# main.net
KiCad netlist of a schematic drawn in Altium Designer
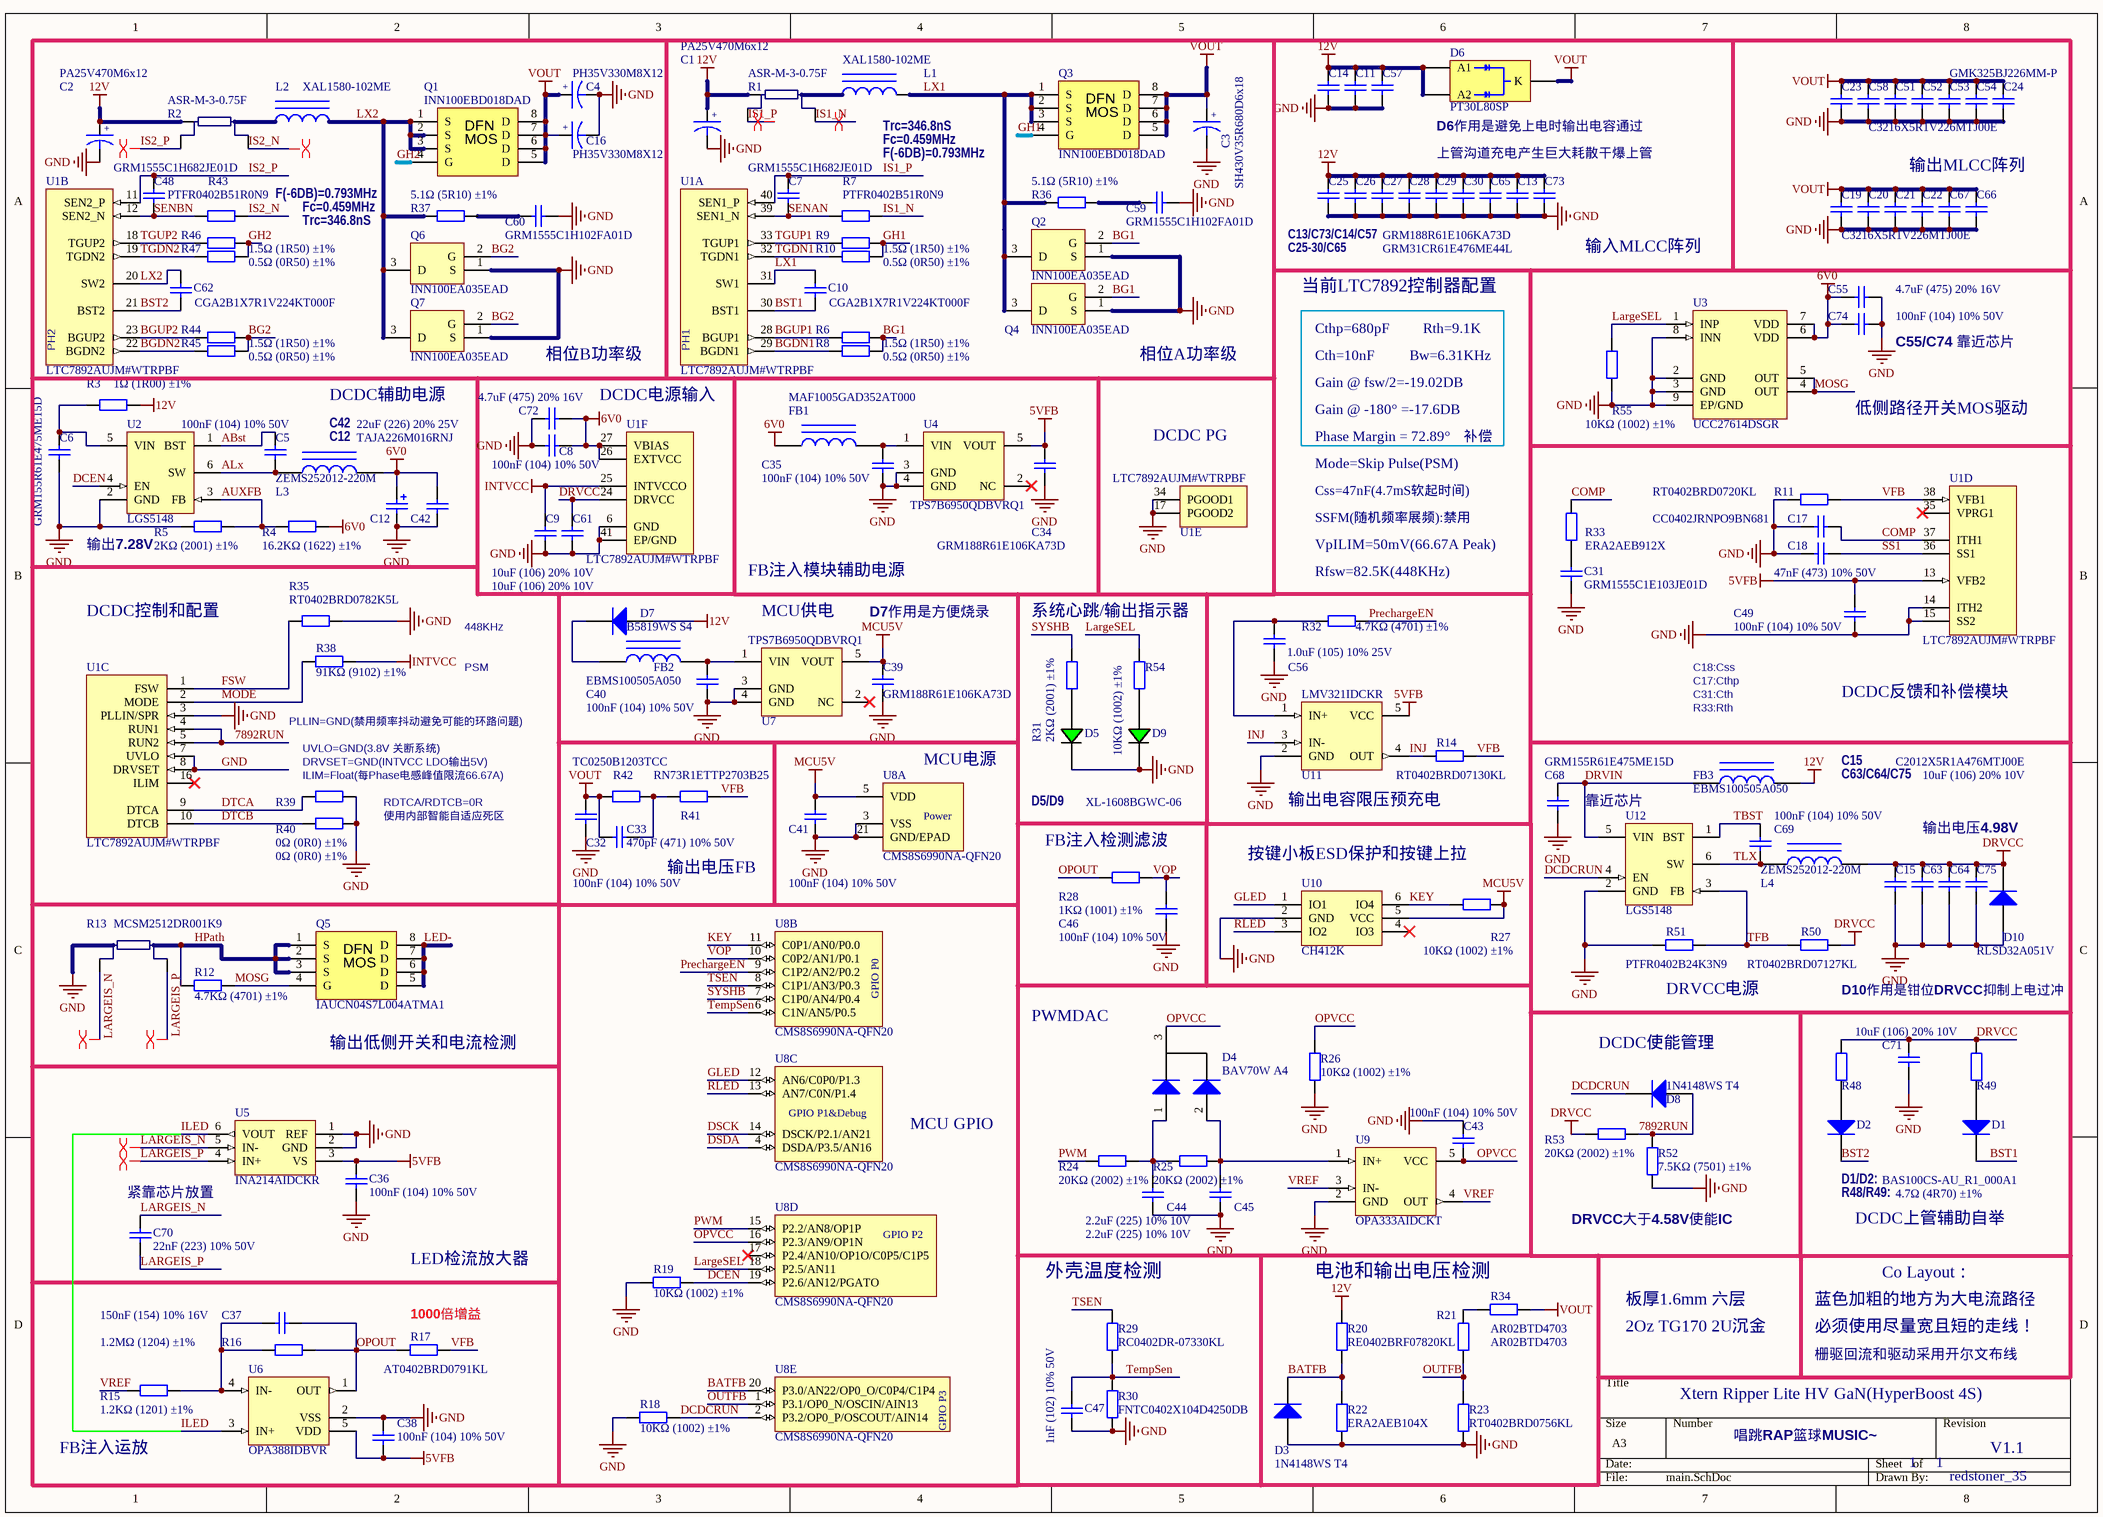
[diagram p0: main.SchDoc]

(export (version "E")
  (design (tool "Eeschema 10.0.6"))
  (components
    (comp (ref "C1")
      (value "PA25V470M6x12")
      (footprint "ElecCap_Hori")
      (description "直插固态电容，耐压25V容量470uF，尺寸D6.3x12")
      (libsource (lib "山猫的集成库20190318") (part "CAP2"))
    )
    (comp (ref "C2")
      (value "PA25V470M6x12")
      (footprint "ElecCap_Hori")
      (description "直插固态电容，耐压25V容量470uF，尺寸D6.3x12")
      (libsource (lib "山猫的集成库20190318") (part "CAP2"))
    )
    (comp (ref "C3")
      (value "SH430V35R680D6x18")
      (footprint "ElecCap_Hori")
      (description "升阳电子 直插特殊尺寸固态电容 680uF ±20% 35V 直径63mm长度18mm 2000Hr@105℃")
      (libsource (lib "山猫的集成库20190318") (part "CAP2"))
    )
    (comp (ref "C4")
      (value "PH35V330M8X12")
      (footprint "CAP-8/3.5")
      (description "125°C 5000Hrs 高温耐受直插固态电容。耐压35V容量330uF，尺寸D8mmxL12mm")
      (libsource (lib "山猫的集成库20190318") (part "CAP2"))
    )
    (comp (ref "C5")
      (value "100nF (104) 10% 50V")
      (footprint "0402_C")
      (description "贴片电容")
      (libsource (lib "Miscellaneous Devices LC") (part "0402 100nF (104) 10% 16V"))
    )
    (comp (ref "C6")
      (value "GRM155R61E475ME15D")
      (footprint "0402_C")
      (description "0402贴片MLCC电容 4.7uF±20% 25V X5R")
      (libsource (lib "Miscellaneous Devices LC") (part "0402 1.0uF (105) 10% 25V"))
    )
    (comp (ref "C7")
      (value "GRM1555C1H682JE01D")
      (footprint "0402_C")
      (description "0402贴片MLCC电容 6.8nF±5% 50V C0G/NP0")
      (libsource (lib "Miscellaneous Devices LC") (part "0402 1nF (102) 10% 50V"))
    )
    (comp (ref "C8")
      (value "100nF (104) 10% 50V")
      (footprint "0402_C")
      (description "贴片电容")
      (libsource (lib "Miscellaneous Devices LC") (part "0402 100nF (104) 10% 16V"))
    )
    (comp (ref "C9")
      (value "10uF (106) 20% 10V")
      (footprint "0402_C")
      (description "贴片电容")
      (libsource (lib "Miscellaneous Devices LC") (part "0402 10uF (106) 20% 6.3V"))
    )
    (comp (ref "C10")
      (value "CGA2B1X7R1V224KT000F")
      (footprint "0402_C")
      (description "车规级 0402贴片MLCC电容 35V 220nF±10% X7R")
      (libsource (lib "Miscellaneous Devices LC") (part "0402 220nF (224) 10% 16V"))
    )
    (comp (ref "C11")
      (value "GRM188R61E106KA73D")
      (footprint "0603_C")
      (description "贴片MLCC电容 25V 10uF±20% X5R")
      (libsource (lib "Miscellaneous Devices LC") (part "0603 10uF (106) 10% 10V"))
    )
    (comp (ref "C12")
      (value "TAJA226M016RNJ")
      (footprint "CASE-A_3216")
      (description "1206钽电容，22uF (226) ±10% 16V")
      (libsource (lib "Miscellaneous Devices LC") (part "3216 10uF (106) 10% 16V"))
    )
    (comp (ref "C13")
      (value "GRM188R61E106KA73D")
      (footprint "0603_C")
      (description "贴片MLCC电容 25V 10uF±20% X5R")
      (libsource (lib "Miscellaneous Devices LC") (part "0603 10uF (106) 10% 10V"))
    )
    (comp (ref "C14")
      (value "GRM188R61E106KA73D")
      (footprint "0603_C")
      (description "贴片MLCC电容 25V 10uF±20% X5R")
      (libsource (lib "Miscellaneous Devices LC") (part "0603 10uF (106) 10% 10V"))
    )
    (comp (ref "C15")
      (value "C2012X5R1A476MTJ00E")
      (footprint "0805_C")
      (description "贴片MLCC电容，X5R 47uF ±20% 10V")
      (libsource (lib "Miscellaneous Devices LC") (part "0805 22uF (226) 20% 25V"))
    )
    (comp (ref "C16")
      (value "PH35V330M8X12")
      (footprint "CAP-8/3.5")
      (description "125°C 5000Hrs 高温耐受直插固态电容。耐压35V容量330uF，尺寸D8mmxL12mm")
      (libsource (lib "山猫的集成库20190318") (part "CAP2"))
    )
    (comp (ref "C17")
      (value "CC0402JRNPO9BN681")
      (footprint "0402_C")
      (description "0402贴片MLCC电容 NP0材质 680pF ±5% 50V")
      (libsource (lib "Miscellaneous Devices LC") (part "0402 1nF (102) 10% 50V"))
    )
    (comp (ref "C18")
      (value "47nF (473) 10% 50V")
      (footprint "0402_C")
      (description "贴片电容")
      (libsource (lib "Miscellaneous Devices LC") (part "0402 100nF (104) 10% 16V"))
    )
    (comp (ref "C19")
      (value "C3216X5R1V226MTJ00E")
      (footprint "1206C")
      (description "TDK MLCC电容 X5R 35V 22uF±20%")
      (fields (field (name "PUBLISHER") "Altium Limited"))
      (libsource (lib "山猫的集成库20190318") (part "Cap"))
    )
    (comp (ref "C20")
      (value "C3216X5R1V226MTJ00E")
      (footprint "1206C")
      (description "TDK MLCC电容 X5R 35V 22uF±20%")
      (fields (field (name "PUBLISHER") "Altium Limited"))
      (libsource (lib "山猫的集成库20190318") (part "Cap"))
    )
    (comp (ref "C21")
      (value "C3216X5R1V226MTJ00E")
      (footprint "1206C")
      (description "TDK MLCC电容 X5R 35V 22uF±20%")
      (fields (field (name "PUBLISHER") "Altium Limited"))
      (libsource (lib "山猫的集成库20190318") (part "Cap"))
    )
    (comp (ref "C22")
      (value "C3216X5R1V226MTJ00E")
      (footprint "1206C")
      (description "TDK MLCC电容 X5R 35V 22uF±20%")
      (fields (field (name "PUBLISHER") "Altium Limited"))
      (libsource (lib "山猫的集成库20190318") (part "Cap"))
    )
    (comp (ref "C23")
      (value "C3216X5R1V226MTJ00E")
      (footprint "1206C")
      (description "TDK MLCC电容 X5R 35V 22uF±20%")
      (fields (field (name "PUBLISHER") "Altium Limited"))
      (libsource (lib "山猫的集成库20190318") (part "Cap"))
    )
    (comp (ref "C24")
      (value "GMK325BJ226MM-P")
      (footprint "1210C")
      (description "1210 MLCC电容 35V 22uF ±20% X5R")
      (fields (field (name "PUBLISHER") "Altium Limited"))
      (libsource (lib "山猫的集成库20190318") (part "Cap"))
    )
    (comp (ref "C25")
      (value "GRM31CR61E476ME44L")
      (footprint "1206C")
      (description "1206尺寸村田MLCC 25V 47uF X5R ±20%")
      (fields (field (name "PUBLISHER") "Altium Limited"))
      (libsource (lib "山猫的集成库20190318") (part "Cap"))
    )
    (comp (ref "C26")
      (value "GRM31CR61E476ME44L")
      (footprint "1206C")
      (description "1206尺寸村田MLCC 25V 47uF X5R ±20%")
      (fields (field (name "PUBLISHER") "Altium Limited"))
      (libsource (lib "山猫的集成库20190318") (part "Cap"))
    )
    (comp (ref "C27")
      (value "GRM31CR61E476ME44L")
      (footprint "1206C")
      (description "1206尺寸村田MLCC 25V 47uF X5R ±20%")
      (fields (field (name "PUBLISHER") "Altium Limited"))
      (libsource (lib "山猫的集成库20190318") (part "Cap"))
    )
    (comp (ref "C28")
      (value "GRM31CR61E476ME44L")
      (footprint "1206C")
      (description "1206尺寸村田MLCC 25V 47uF X5R ±20%")
      (fields (field (name "PUBLISHER") "Altium Limited"))
      (libsource (lib "山猫的集成库20190318") (part "Cap"))
    )
    (comp (ref "C29")
      (value "GRM31CR61E476ME44L")
      (footprint "1206C")
      (description "1206尺寸村田MLCC 25V 47uF X5R ±20%")
      (fields (field (name "PUBLISHER") "Altium Limited"))
      (libsource (lib "山猫的集成库20190318") (part "Cap"))
    )
    (comp (ref "C30")
      (value "GRM31CR61E476ME44L")
      (footprint "1206C")
      (description "1206尺寸村田MLCC 25V 47uF X5R ±20%")
      (fields (field (name "PUBLISHER") "Altium Limited"))
      (libsource (lib "山猫的集成库20190318") (part "Cap"))
    )
    (comp (ref "C31")
      (value "GRM1555C1E103JE01D")
      (footprint "0402_C")
      (description "0402贴片MLCC电容 10nF±5% 25V C0G/NP0")
      (libsource (lib "Miscellaneous Devices LC") (part "0402 6.8nF (682) 10% 50V"))
    )
    (comp (ref "C32")
      (value "100nF (104) 10% 50V")
      (footprint "0402_C")
      (description "贴片电容")
      (libsource (lib "Miscellaneous Devices LC") (part "0402 100nF (104) 10% 16V"))
    )
    (comp (ref "C33")
      (value "470pF (471) 10% 50V")
      (footprint "0402_C")
      (description "贴片电容")
      (libsource (lib "Miscellaneous Devices LC") (part "0402 470pF (471) 10% 50V"))
    )
    (comp (ref "C34")
      (value "GRM188R61E106KA73D")
      (footprint "0603_C")
      (description "贴片MLCC电容 25V 10uF±20% X5R")
      (libsource (lib "Miscellaneous Devices LC") (part "0603 10uF (106) 10% 10V"))
    )
    (comp (ref "C35")
      (value "100nF (104) 10% 50V")
      (footprint "0402_C")
      (description "贴片电容")
      (libsource (lib "Miscellaneous Devices LC") (part "0402 100nF (104) 10% 16V"))
    )
    (comp (ref "C36")
      (value "100nF (104) 10% 50V")
      (footprint "0402_C")
      (description "贴片电容")
      (libsource (lib "Miscellaneous Devices LC") (part "0402 100nF (104) 10% 16V"))
    )
    (comp (ref "C37")
      (value "150nF (154) 10% 16V")
      (footprint "0402_C")
      (description "贴片电容")
      (libsource (lib "Miscellaneous Devices LC") (part "0402 100nF (104) 10% 16V"))
    )
    (comp (ref "C38")
      (value "100nF (104) 10% 50V")
      (footprint "0402_C")
      (description "贴片电容")
      (libsource (lib "Miscellaneous Devices LC") (part "0402 100nF (104) 10% 16V"))
    )
    (comp (ref "C39")
      (value "GRM188R61E106KA73D")
      (footprint "0603_C")
      (description "贴片MLCC电容 25V 10uF±20% X5R")
      (libsource (lib "Miscellaneous Devices LC") (part "0603 10uF (106) 10% 10V"))
    )
    (comp (ref "C40")
      (value "100nF (104) 10% 50V")
      (footprint "0402_C")
      (description "贴片电容")
      (libsource (lib "Miscellaneous Devices LC") (part "0402 100nF (104) 10% 16V"))
    )
    (comp (ref "C41")
      (value "100nF (104) 10% 50V")
      (footprint "0402_C")
      (description "贴片电容")
      (libsource (lib "Miscellaneous Devices LC") (part "0402 100nF (104) 10% 16V"))
    )
    (comp (ref "C42")
      (value "22uF (226) 20% 25V")
      (footprint "0805_C")
      (description "贴片电容")
      (libsource (lib "Miscellaneous Devices LC") (part "0805 22uF (226) 20% 25V"))
    )
    (comp (ref "C43")
      (value "100nF (104) 10% 50V")
      (footprint "0402_C")
      (description "贴片电容")
      (libsource (lib "Miscellaneous Devices LC") (part "0402 100nF (104) 10% 16V"))
    )
    (comp (ref "C44")
      (value "2.2uF (225) 10% 10V")
      (footprint "0402_C")
      (description "贴片电容")
      (libsource (lib "Miscellaneous Devices LC") (part "0402 1.0uF (105) 10% 25V"))
    )
    (comp (ref "C45")
      (value "2.2uF (225) 10% 10V")
      (footprint "0402_C")
      (description "贴片电容")
      (libsource (lib "Miscellaneous Devices LC") (part "0402 1.0uF (105) 10% 25V"))
    )
    (comp (ref "C46")
      (value "100nF (104) 10% 50V")
      (footprint "0402_C")
      (description "贴片电容")
      (libsource (lib "Miscellaneous Devices LC") (part "0402 100nF (104) 10% 16V"))
    )
    (comp (ref "C47")
      (value "1nF (102) 10% 50V")
      (footprint "0402_C")
      (description "贴片电容")
      (libsource (lib "Miscellaneous Devices LC") (part "0402 1nF (102) 10% 50V"))
    )
    (comp (ref "C48")
      (value "GRM1555C1H682JE01D")
      (footprint "0402_C")
      (description "0402贴片MLCC电容 6.8nF±5% 50V C0G/NP0")
      (libsource (lib "Miscellaneous Devices LC") (part "0402 1nF (102) 10% 50V"))
    )
    (comp (ref "C49")
      (value "100nF (104) 10% 50V")
      (footprint "0402_C")
      (description "贴片电容")
      (libsource (lib "Miscellaneous Devices LC") (part "0402 100nF (104) 10% 16V"))
    )
    (comp (ref "C51")
      (value "C3216X5R1V226MTJ00E")
      (footprint "1206C")
      (description "TDK MLCC电容 X5R 35V 22uF±20%")
      (fields (field (name "PUBLISHER") "Altium Limited"))
      (libsource (lib "山猫的集成库20190318") (part "Cap"))
    )
    (comp (ref "C52")
      (value "C3216X5R1V226MTJ00E")
      (footprint "1206C")
      (description "TDK MLCC电容 X5R 35V 22uF±20%")
      (fields (field (name "PUBLISHER") "Altium Limited"))
      (libsource (lib "山猫的集成库20190318") (part "Cap"))
    )
    (comp (ref "C53")
      (value "C3216X5R1V226MTJ00E")
      (footprint "1206C")
      (description "TDK MLCC电容 X5R 35V 22uF±20%")
      (fields (field (name "PUBLISHER") "Altium Limited"))
      (libsource (lib "山猫的集成库20190318") (part "Cap"))
    )
    (comp (ref "C54")
      (value "C3216X5R1V226MTJ00E")
      (footprint "1206C")
      (description "TDK MLCC电容 X5R 35V 22uF±20%")
      (fields (field (name "PUBLISHER") "Altium Limited"))
      (libsource (lib "山猫的集成库20190318") (part "Cap"))
    )
    (comp (ref "C55")
      (value "4.7uF (475) 20% 16V")
      (footprint "0402_C")
      (description "贴片电容")
      (libsource (lib "Miscellaneous Devices LC") (part "0402 1.0uF (105) 10% 25V"))
    )
    (comp (ref "C56")
      (value "1.0uF (105) 10% 25V")
      (footprint "0402_C")
      (description "贴片电容")
      (libsource (lib "Miscellaneous Devices LC") (part "0402 1.0uF (105) 10% 25V"))
    )
    (comp (ref "C57")
      (value "GRM31CR61E476ME44L")
      (footprint "1206C")
      (description "1206尺寸村田MLCC 25V 47uF X5R ±20%")
      (fields (field (name "PUBLISHER") "Altium Limited"))
      (libsource (lib "山猫的集成库20190318") (part "Cap"))
    )
    (comp (ref "C58")
      (value "C3216X5R1V226MTJ00E")
      (footprint "1206C")
      (description "TDK MLCC电容 X5R 35V 22uF±20%")
      (fields (field (name "PUBLISHER") "Altium Limited"))
      (libsource (lib "山猫的集成库20190318") (part "Cap"))
    )
    (comp (ref "C59")
      (value "GRM1555C1H102FA01D")
      (footprint "0402_C")
      (description "村田0402贴片MLCC电容 1nF ±1% 50V C0G")
      (libsource (lib "Miscellaneous Devices LC") (part "0402 1nF (102) 10% 50V"))
    )
    (comp (ref "C60")
      (value "GRM1555C1H102FA01D")
      (footprint "0402_C")
      (description "村田0402贴片MLCC电容 1nF ±1% 50V C0G")
      (libsource (lib "Miscellaneous Devices LC") (part "0402 1nF (102) 10% 50V"))
    )
    (comp (ref "C61")
      (value "10uF (106) 20% 10V")
      (footprint "0402_C")
      (description "贴片电容")
      (libsource (lib "Miscellaneous Devices LC") (part "0402 10uF (106) 20% 6.3V"))
    )
    (comp (ref "C62")
      (value "CGA2B1X7R1V224KT000F")
      (footprint "0402_C")
      (description "车规级 0402贴片MLCC电容 35V 220nF±10% X7R")
      (libsource (lib "Miscellaneous Devices LC") (part "0402 220nF (224) 10% 16V"))
    )
    (comp (ref "C63")
      (value "10uF (106) 20% 10V")
      (footprint "0402_C")
      (description "贴片电容")
      (libsource (lib "Miscellaneous Devices LC") (part "0402 4.7uF (475) 20% 10V"))
    )
    (comp (ref "C64")
      (value "10uF (106) 20% 10V")
      (footprint "0402_C")
      (description "贴片电容")
      (libsource (lib "Miscellaneous Devices LC") (part "0402 4.7uF (475) 20% 10V"))
    )
    (comp (ref "C65")
      (value "GRM31CR61E476ME44L")
      (footprint "1206C")
      (description "1206尺寸村田MLCC 25V 47uF X5R ±20%")
      (fields (field (name "PUBLISHER") "Altium Limited"))
      (libsource (lib "山猫的集成库20190318") (part "Cap"))
    )
    (comp (ref "C66")
      (value "C3216X5R1V226MTJ00E")
      (footprint "1206C")
      (description "TDK MLCC电容 X5R 35V 22uF±20%")
      (fields (field (name "PUBLISHER") "Altium Limited"))
      (libsource (lib "山猫的集成库20190318") (part "Cap"))
    )
    (comp (ref "C67")
      (value "C3216X5R1V226MTJ00E")
      (footprint "1206C")
      (description "TDK MLCC电容 X5R 35V 22uF±20%")
      (fields (field (name "PUBLISHER") "Altium Limited"))
      (libsource (lib "山猫的集成库20190318") (part "Cap"))
    )
    (comp (ref "C68")
      (value "GRM155R61E475ME15D")
      (footprint "0402_C")
      (description "0402贴片MLCC电容 4.7uF±20% 25V X5R")
      (libsource (lib "Miscellaneous Devices LC") (part "0402 1.0uF (105) 10% 25V"))
    )
    (comp (ref "C69")
      (value "100nF (104) 10% 50V")
      (footprint "0402_C")
      (description "贴片电容")
      (libsource (lib "Miscellaneous Devices LC") (part "0402 100nF (104) 10% 16V"))
    )
    (comp (ref "C70")
      (value "22nF (223) 10% 50V")
      (footprint "0402_C")
      (description "贴片电容")
      (libsource (lib "Miscellaneous Devices LC") (part "0402 10nF (103) 10% 50V"))
    )
    (comp (ref "C71")
      (value "10uF (106) 20% 10V")
      (footprint "0402_C")
      (description "贴片电容")
      (libsource (lib "Miscellaneous Devices LC") (part "0402 10uF (106) 20% 6.3V"))
    )
    (comp (ref "C72")
      (value "4.7uF (475) 20% 16V")
      (footprint "0402_C")
      (description "贴片电容")
      (libsource (lib "Miscellaneous Devices LC") (part "0402 1.0uF (105) 10% 25V"))
    )
    (comp (ref "C73")
      (value "GRM188R61E106KA73D")
      (footprint "0603_C")
      (description "贴片MLCC电容 25V 10uF±20% X5R")
      (libsource (lib "Miscellaneous Devices LC") (part "0603 10uF (106) 10% 10V"))
    )
    (comp (ref "C74")
      (value "100nF (104) 10% 50V")
      (footprint "0402_C")
      (description "贴片电容")
      (libsource (lib "Miscellaneous Devices LC") (part "0402 100nF (104) 10% 16V"))
    )
    (comp (ref "C75")
      (value "10uF (106) 20% 10V")
      (footprint "0402_C")
      (description "贴片电容")
      (libsource (lib "Miscellaneous Devices LC") (part "0402 4.7uF (475) 20% 10V"))
    )
    (comp (ref "D1")
      (value "BAS100CS-AU_R1_000A1")
      (footprint "SOD-323")
      (description "二极管")
      (libsource (lib "Miscellaneous Devices LC") (part "SOD-323 1N4148WS T4"))
    )
    (comp (ref "D2")
      (value "BAS100CS-AU_R1_000A1")
      (footprint "SOD-323")
      (description "二极管")
      (libsource (lib "Miscellaneous Devices LC") (part "SOD-323 1N4148WS T4"))
    )
    (comp (ref "D3")
      (value "1N4148WS T4")
      (footprint "SOD-323")
      (description "二极管")
      (libsource (lib "Miscellaneous Devices LC") (part "SOD-323 1N4148WS T4"))
    )
    (comp (ref "D4")
      (value "BAV70W A4")
      (footprint "SC70-3")
      (description "开关二极管")
      (libsource (lib "Miscellaneous Devices LC") (part "SOT-23 BAV70 A4"))
    )
    (comp (ref "D5")
      (value "XL-1608BGWC-06")
      (footprint "LED-0402")
      (description "0603(1608)贴片冰蓝色发光二极管 2.7-3.4V 20mA")
      (libsource (lib "custom") (part "LED0402"))
    )
    (comp (ref "D6")
      (value "PT30L80SP")
      (footprint "TO277")
      (description "30A 80V 肖特基二极管")
      (libsource (lib "custom") (part "SB2045L"))
    )
    (comp (ref "D7")
      (value "B5819WS S4")
      (footprint "SOD-323")
      (description "二极管")
      (libsource (lib "Miscellaneous Devices LC") (part "SOD-323 1N4148WS T4"))
    )
    (comp (ref "D8")
      (value "1N4148WS T4")
      (footprint "SOD-323")
      (description "二极管")
      (libsource (lib "Miscellaneous Devices LC") (part "SOD-323 1N4148WS T4"))
    )
    (comp (ref "D9")
      (value "XL-1608BGWC-06")
      (footprint "LED-0402")
      (description "0603(1608)贴片冰蓝色发光二极管 2.7-3.4V 20mA")
      (libsource (lib "custom") (part "LED0402"))
    )
    (comp (ref "D10")
      (value "RLSD32A051V")
      (footprint "SOD-323")
      (description "单向TVS二极管 5V工作电压 峰值脉冲电流：21A@8/20us")
      (libsource (lib "Miscellaneous Devices LC") (part "SOD-323 1N4148WS T4"))
    )
    (comp (ref "FB1")
      (value "MAF1005GAD352AT000")
      (footprint "0402_L")
      (description "贴片铁氧体磁珠 270mA 500R@100MHz")
      (libsource (lib "Miscellaneous Devices LC") (part "0402 12nH  5%"))
    )
    (comp (ref "FB2")
      (value "EBMS100505A050")
      (footprint "0402_L")
      (description "贴片磁珠 200mA 5R±25% 100MHz")
      (libsource (lib "Miscellaneous Devices LC") (part "0402 12nH  5%"))
    )
    (comp (ref "FB3")
      (value "EBMS100505A050")
      (footprint "0402_L")
      (description "贴片磁珠 200mA 5R±25% 100MHz")
      (libsource (lib "Miscellaneous Devices LC") (part "0402 12nH  5%"))
    )
    (comp (ref "L1")
      (value "XAL1580-102ME")
      (footprint "XAL1580_xxxME")
      (description "线艺XAL系列电感")
      (fields (field (name "PUBLISHER") "Altium Limited"))
      (libsource (lib "") (part "Inductor Iron_1"))
    )
    (comp (ref "L2")
      (value "XAL1580-102ME")
      (footprint "XAL1580_xxxME")
      (description "线艺XAL系列电感")
      (fields (field (name "PUBLISHER") "Altium Limited"))
      (libsource (lib "") (part "Inductor Iron_1"))
    )
    (comp (ref "L3")
      (value "ZEMS252012-220M")
      (footprint "SWPA252010S")
      (description "一体成型TCORE热压功率电感 2.5x2.0mm尺寸 1.0mm高度 22uH 0.78Ω 1.2A")
      (fields (field (name "PUBLISHER") "Altium Limited"))
      (libsource (lib "Miscellaneous Devices") (part "Inductor Iron"))
    )
    (comp (ref "L4")
      (value "ZEMS252012-220M")
      (footprint "SWPA252010S")
      (description "一体成型TCORE热压功率电感 2.5x2.0mm尺寸 1.0mm高度 22uH 0.78Ω 1.2A")
      (fields (field (name "PUBLISHER") "Altium Limited"))
      (libsource (lib "Miscellaneous Devices") (part "Inductor Iron"))
    )
    (comp (ref "Q1")
      (value "INN100EBD018DAD")
      (footprint "EN-FCLGA-8_L6.0-W5.0-P1.27-BL-EP")
      (description "基于先进GaN技术的100V硅基氮化镓增强型HEMT晶体管，采用En-FCLGA 5mm x 6mm 封装。")
      (libsource (lib "custom") (part "SON/DFN5x6 MOS"))
    )
    (comp (ref "Q2")
      (value "INN100EA035EAD")
      (footprint "FCLGA-8_L3.3-W3.3_INN100EA070DAD")
      (description "100V Enhancement-mode GaN Power Transistor, 2.7mΩ Gen3.5")
      (libsource (lib "custom") (part "INN100EA035A-C"))
    )
    (comp (ref "Q3")
      (value "INN100EBD018DAD")
      (footprint "EN-FCLGA-8_L6.0-W5.0-P1.27-BL-EP")
      (description "基于先进GaN技术的100V硅基氮化镓增强型HEMT晶体管，采用En-FCLGA 5mm x 6mm 封装。")
      (libsource (lib "custom") (part "SON/DFN5x6 MOS"))
    )
    (comp (ref "Q4")
      (value "INN100EA035EAD")
      (footprint "FCLGA-8_L3.3-W3.3_INN100EA070DAD")
      (description "100V Enhancement-mode GaN Power Transistor, 2.7mΩ Gen3.5")
      (libsource (lib "custom") (part "INN100EA035A-C"))
    )
    (comp (ref "Q5")
      (value "IAUCN04S7L004ATMA1")
      (footprint "SON/DFN5x6(MOS)")
      (description "0.44mΩ 40V 逻辑电平 OptiMOS 7 车规级MOSFET")
      (libsource (lib "custom") (part "SON/DFN5x6 MOS"))
    )
    (comp (ref "Q6")
      (value "INN100EA035EAD")
      (footprint "FCLGA-8_L3.3-W3.3_INN100EA070DAD")
      (description "100V Enhancement-mode GaN Power Transistor, 2.7mΩ Gen3.5")
      (libsource (lib "custom") (part "INN100EA035A-C"))
    )
    (comp (ref "Q7")
      (value "INN100EA035EAD")
      (footprint "FCLGA-8_L3.3-W3.3_INN100EA070DAD")
      (description "100V Enhancement-mode GaN Power Transistor, 2.7mΩ Gen3.5")
      (libsource (lib "custom") (part "INN100EA035A-C"))
    )
    (comp (ref "R1")
      (value "ASR-M-3-0.75F")
      (footprint "2512-Virtual4Wire")
      (description "业展ASR系列精密检流电阻，2512 0.75mΩ±1% 锰铜材质 <50ppm/K P70℃=5W")
      (libsource (lib "custom") (part "shunt"))
    )
    (comp (ref "R2")
      (value "ASR-M-3-0.75F")
      (footprint "2512-Virtual4Wire")
      (description "业展ASR系列精密检流电阻，2512 0.75mΩ±1% 锰铜材质 <50ppm/K P70℃=5W")
      (libsource (lib "custom") (part "shunt"))
    )
    (comp (ref "R3")
      (value "1Ω (1R00) ±1%")
      (footprint "0402_R")
      (description "贴片电阻")
      (libsource (lib "Miscellaneous Devices LC") (part "0402 1Ω (1R00) 1%"))
    )
    (comp (ref "R4")
      (value "16.2KΩ (1622) ±1%")
      (footprint "0402_R")
      (description "贴片电阻")
      (libsource (lib "Miscellaneous Devices LC") (part "0402 10KΩ (1002) 1%"))
    )
    (comp (ref "R5")
      (value "2KΩ (2001) ±1%")
      (footprint "0402_R")
      (description "贴片电阻")
      (libsource (lib "Miscellaneous Devices LC") (part "0402 10KΩ (1002) 1%"))
    )
    (comp (ref "R6")
      (value "1.5Ω (1R50) ±1%")
      (footprint "0402_R")
      (description "贴片电阻")
      (libsource (lib "Miscellaneous Devices LC") (part "0402 1Ω (1R00) 1%"))
    )
    (comp (ref "R7")
      (value "PTFR0402B51R0N9")
      (footprint "0402_R")
      (description "0402高精密低温飘薄膜贴片电阻 51Ω ±0.1% 62.5mW 25PPM")
      (libsource (lib "Miscellaneous Devices LC") (part "0402 10Ω (10R0) 1%"))
    )
    (comp (ref "R8")
      (value "0.5Ω (0R50) ±1%")
      (footprint "0402_R")
      (description "贴片电阻")
      (libsource (lib "Miscellaneous Devices LC") (part "0402 1Ω (1R00) 1%"))
    )
    (comp (ref "R9")
      (value "1.5Ω (1R50) ±1%")
      (footprint "0402_R")
      (description "贴片电阻")
      (libsource (lib "Miscellaneous Devices LC") (part "0402 1Ω (1R00) 1%"))
    )
    (comp (ref "R10")
      (value "0.5Ω (0R50) ±1%")
      (footprint "0402_R")
      (description "贴片电阻")
      (libsource (lib "Miscellaneous Devices LC") (part "0402 1Ω (1R00) 1%"))
    )
    (comp (ref "R11")
      (value "RT0402BRD0720KL")
      (footprint "0402_R")
      (description "0402贴片薄膜高精密电阻 20KΩ ±0.1% 62.5mW 25PPM")
      (libsource (lib "Miscellaneous Devices LC") (part "0402 20KΩ (2002) 1%"))
    )
    (comp (ref "R12")
      (value "4.7KΩ (4701) ±1%")
      (footprint "0402_R")
      (description "贴片电阻")
      (libsource (lib "Miscellaneous Devices LC") (part "0402 10KΩ (1002) 1%"))
    )
    (comp (ref "R13")
      (value "MCSM2512DR001K9")
      (footprint "2512-Virtual4Wire")
      (description "精密低温漂束焊模压合金检流电阻 车规级别 1.0mΩ ±0.5% 3W")
      (libsource (lib "custom") (part "shunt"))
    )
    (comp (ref "R14")
      (value "RT0402BRD07130KL")
      (footprint "0402_R")
      (description "0402贴片薄膜高精密电阻 130KΩ ±0.1% 62.5mW 25PPM")
      (libsource (lib "") (part "0402 100KΩ (1003) 1%_1"))
    )
    (comp (ref "R15")
      (value "1.2KΩ (1201) ±1%")
      (footprint "0402_R")
      (description "贴片电阻")
      (libsource (lib "Miscellaneous Devices LC") (part "0402 470Ω (4700) 1%"))
    )
    (comp (ref "R16")
      (value "1.2MΩ (1204) ±1%")
      (footprint "0402_R")
      (description "贴片电阻")
      (libsource (lib "Miscellaneous Devices LC") (part "0402 1MΩ (1004) 1%"))
    )
    (comp (ref "R17")
      (value "AT0402BRD0791KL")
      (footprint "0402_R")
      (description "0402贴片薄膜高精密电阻 91KΩ ±0.1% 62.5mW 25PPM")
      (libsource (lib "") (part "0402 100KΩ (1003) 1%_1"))
    )
    (comp (ref "R18")
      (value "10KΩ (1002) ±1%")
      (footprint "0402_R")
      (description "贴片电阻")
      (libsource (lib "Miscellaneous Devices LC") (part "0402 10KΩ (1002) 1%"))
    )
    (comp (ref "R19")
      (value "10KΩ (1002) ±1%")
      (footprint "0402_R")
      (description "贴片电阻")
      (libsource (lib "") (part "0402 10KΩ (1002) 1%_2"))
    )
    (comp (ref "R20")
      (value "RE0402BRF07820KL")
      (footprint "0402_R")
      (description "0402精密低温飘贴片电阻 820K±0.1% 62.5mW")
      (libsource (lib "Miscellaneous Devices LC") (part "0402 680Ω (6800) 1%"))
    )
    (comp (ref "R21")
      (value "AR02BTD4703")
      (footprint "0402_R")
      (description "0402 贴片薄膜高精密低温飘电阻 470KΩ±0.1% 25PPM")
      (libsource (lib "Miscellaneous Devices LC") (part "0402 470KΩ (4703) 1%"))
    )
    (comp (ref "R22")
      (value "ERA2AEB104X")
      (footprint "0402_R")
      (description "松下 0402精密低温飘贴片电阻 100±0.1% 62.5mW")
      (libsource (lib "Miscellaneous Devices LC") (part "0402 100KΩ (1003) 1%"))
    )
    (comp (ref "R23")
      (value "RT0402BRD0756KL")
      (footprint "0402_R")
      (description "0402薄膜贴片高精密电阻 56K±0.1% 62.5mW")
      (libsource (lib "Miscellaneous Devices LC") (part "0402 100KΩ (1003) 1%"))
    )
    (comp (ref "R24")
      (value "20KΩ (2002) ±1%")
      (footprint "0402_R")
      (description "贴片电阻")
      (libsource (lib "") (part "0402 10KΩ (1002) 1%_2"))
    )
    (comp (ref "R25")
      (value "20KΩ (2002) ±1%")
      (footprint "0402_R")
      (description "贴片电阻")
      (libsource (lib "Miscellaneous Devices LC") (part "0402 20KΩ (2002) 1%"))
    )
    (comp (ref "R26")
      (value "10KΩ (1002) ±1%")
      (footprint "0402_R")
      (description "贴片电阻")
      (libsource (lib "") (part "0402 10KΩ (1002) 1%_1"))
    )
    (comp (ref "R27")
      (value "10KΩ (1002) ±1%")
      (footprint "0402_R")
      (description "贴片电阻")
      (libsource (lib "") (part "0402 10KΩ (1002) 1%_2"))
    )
    (comp (ref "R28")
      (value "1KΩ (1001) ±1%")
      (footprint "0402_R")
      (description "贴片电阻")
      (libsource (lib "Miscellaneous Devices LC") (part "0402 1KΩ (1001) 1%"))
    )
    (comp (ref "R29")
      (value "RC0402DR-07330KL")
      (footprint "0402_R")
      (description "0402厚膜较高精度贴片电阻 330KΩ±0.5% 62.5mW")
      (libsource (lib "Miscellaneous Devices LC") (part "0402 330KΩ (3303) 1%"))
    )
    (comp (ref "R30")
      (value "FNTC0402X104D4250DB")
      (footprint "0402_R")
      (description "0402尺寸贴片式NTC热敏电阻 B25-85℃=4310±0.5% R25=100KΩ±0.5%")
      (libsource (lib "Miscellaneous Devices LC") (part "0402 100KΩ (1003) 1%"))
    )
    (comp (ref "R31")
      (value "2KΩ (2001) ±1%")
      (footprint "0402_R")
      (description "贴片电阻")
      (libsource (lib "Miscellaneous Devices LC") (part "0402 2KΩ (2001) 1%"))
    )
    (comp (ref "R32")
      (value "4.7KΩ (4701) ±1%")
      (footprint "0402_R")
      (description "贴片电阻")
      (libsource (lib "Miscellaneous Devices LC") (part "0402 20KΩ (2002) 1%"))
    )
    (comp (ref "R33")
      (value "ERA2AEB912X")
      (footprint "0402_R")
      (description "松下高精密0402贴片薄膜电阻 9.1KΩ ±0.1% 62.5mW 5PPM")
      (libsource (lib "") (part "0402 10KΩ (1002) 1%_1"))
    )
    (comp (ref "R34")
      (value "AR02BTD4703")
      (footprint "0402_R")
      (description "0402 贴片薄膜高精密低温飘电阻 470KΩ±0.1% 25PPM")
      (libsource (lib "") (part "0402 10KΩ (1002) 1%_2"))
    )
    (comp (ref "R35")
      (value "RT0402BRD0782K5L")
      (footprint "0402_R")
      (description "薄膜低温飘高精密电阻 82.5KΩ (8242) ± 0.1% 25PPM")
      (libsource (lib "") (part "0402 100KΩ (1003) 1%_1"))
    )
    (comp (ref "R36")
      (value "5.1Ω (5R10) ±1%")
      (footprint "0603_R")
      (description "贴片电阻")
      (libsource (lib "Miscellaneous Devices LC") (part "0603 2.2Ω (2R20) 1%"))
    )
    (comp (ref "R37")
      (value "5.1Ω (5R10) ±1%")
      (footprint "0603_R")
      (description "贴片电阻")
      (libsource (lib "Miscellaneous Devices LC") (part "0603 2.2Ω (2R20) 1%"))
    )
    (comp (ref "R38")
      (value "91KΩ (9102) ±1%")
      (footprint "0402_R")
      (description "贴片电阻")
      (libsource (lib "") (part "0402 100KΩ (1003) 1%_1"))
    )
    (comp (ref "R39")
      (value "0Ω (0R0) ±1%")
      (footprint "0402_R")
      (description "贴片电阻")
      (libsource (lib "Miscellaneous Devices LC") (part "0402 0Ω (0R0) 1%"))
    )
    (comp (ref "R40")
      (value "0Ω (0R0) ±1%")
      (footprint "0402_R")
      (description "贴片电阻")
      (libsource (lib "Miscellaneous Devices LC") (part "0402 0Ω (0R0) 1%"))
    )
    (comp (ref "R41")
      (value "RN73R1ETTP2703B25")
      (footprint "0402_R")
      (description "KOA RN73系列0402贴片薄膜高精密电阻 270KΩ±0.1% 62.5mW ±25PPM")
      (libsource (lib "Miscellaneous Devices LC") (part "0402 200KΩ (2003) 1%"))
    )
    (comp (ref "R42")
      (value "TC0250B1203TCC")
      (footprint "0402_R")
      (description "镍铬薄膜高精密0402贴片电阻 120KΩ ±0.1% 25PPM")
      (libsource (lib "Miscellaneous Devices LC") (part "0402 120KΩ (1203) 1%"))
    )
    (comp (ref "R43")
      (value "PTFR0402B51R0N9")
      (footprint "0402_R")
      (description "0402高精密低温飘薄膜贴片电阻 51Ω ±0.1% 62.5mW 25PPM")
      (libsource (lib "Miscellaneous Devices LC") (part "0402 10Ω (10R0) 1%"))
    )
    (comp (ref "R44")
      (value "1.5Ω (1R50) ±1%")
      (footprint "0402_R")
      (description "贴片电阻")
      (libsource (lib "Miscellaneous Devices LC") (part "0402 1Ω (1R00) 1%"))
    )
    (comp (ref "R45")
      (value "0.5Ω (0R50) ±1%")
      (footprint "0402_R")
      (description "贴片电阻")
      (libsource (lib "Miscellaneous Devices LC") (part "0402 1Ω (1R00) 1%"))
    )
    (comp (ref "R46")
      (value "1.5Ω (1R50) ±1%")
      (footprint "0402_R")
      (description "贴片电阻")
      (libsource (lib "Miscellaneous Devices LC") (part "0402 1Ω (1R00) 1%"))
    )
    (comp (ref "R47")
      (value "0.5Ω (0R50) ±1%")
      (footprint "0402_R")
      (description "贴片电阻")
      (libsource (lib "Miscellaneous Devices LC") (part "0402 1Ω (1R00) 1%"))
    )
    (comp (ref "R48")
      (value "4.7Ω (4R70) ±1%")
      (footprint "0402_R")
      (description "贴片电阻")
      (libsource (lib "") (part "0402 1Ω (1R00) 1%_1"))
    )
    (comp (ref "R49")
      (value "4.7Ω (4R70) ±1%")
      (footprint "0402_R")
      (description "贴片电阻")
      (libsource (lib "") (part "0402 1Ω (1R00) 1%_2"))
    )
    (comp (ref "R50")
      (value "RT0402BRD07127KL")
      (footprint "0402_R")
      (description "精密高稳定性0402贴片电阻 127KΩ ±0.1% 25PPM")
      (libsource (lib "Miscellaneous Devices LC") (part "0402 27KΩ (2702) 1%"))
    )
    (comp (ref "R51")
      (value "PTFR0402B24K3N9")
      (footprint "0402_R")
      (description "高精密高稳定性0402贴片电阻 24.3KΩ ±0.1% 5PPM")
      (libsource (lib "Miscellaneous Devices LC") (part "0402 4.7KΩ (4701) 1%"))
    )
    (comp (ref "R52")
      (value "7.5KΩ (7501) ±1%")
      (footprint "0402_R")
      (description "贴片电阻")
      (libsource (lib "Miscellaneous Devices LC") (part "0402 8.2KΩ (8201) 1%"))
    )
    (comp (ref "R53")
      (value "20KΩ (2002) ±1%")
      (footprint "0402_R")
      (description "贴片电阻")
      (libsource (lib "Miscellaneous Devices LC") (part "0402 20KΩ (2002) 1%"))
    )
    (comp (ref "R54")
      (value "10KΩ (1002) ±1%")
      (footprint "0402_R")
      (description "贴片电阻")
      (libsource (lib "") (part "0402 10KΩ (1002) 1%_1"))
    )
    (comp (ref "R55")
      (value "10KΩ (1002) ±1%")
      (footprint "0402_R")
      (description "贴片电阻")
      (libsource (lib "") (part "0402 10KΩ (1002) 1%_1"))
    )
    (comp (ref "U1")
      (value "LTC7892AUJM#WTRPBF")
      (footprint "UJM0040A")
      (description "Low IQ  , Dual, 2-Phase Synchronous Boost Controller for GaN FETs, AEC-Q100 Certified")
      (libsource (lib "custom") (part "LTC7892RUJM"))
    )
    (comp (ref "U2")
      (value "LGS5148")
      (footprint "SOT95P245X110-6N")
      (description "48V输入，600mA同步降压转换器，SOT-23-6封装")
      (libsource (lib "custom") (part "LGS5148"))
    )
    (comp (ref "U3")
      (value "UCC27614DSGR")
      (footprint "DSG0008A")
      (description "10A峰值电流驱动能力的单路低侧栅极驱动器，17.5nS典型传播延迟，WSON8封装")
      (libsource (lib "custom") (part "UCC27614DSGR"))
    )
    (comp (ref "U4")
      (value "TPS7B6950QDBVRQ1")
      (footprint "SOT95P245X110-5N")
      (description "150mA 40V max input Ultra low Iq LDO,fixed   5V output AECQ100 Qualified")
      (libsource (lib "custom") (part "TPS7B6933DBVR"))
    )
    (comp (ref "U5")
      (value "INA214AIDCKR")
      (footprint "SC70-6")
      (description "100V/V增益 26V最高共模电压，高低测通用双向高精度检流放大器 SC70-6封装")
      (libsource (lib "custom") (part "INA199A2DCKR"))
    )
    (comp (ref "U6")
      (value "OPA388IDBVR")
      (footprint "SOT95P245X110-5N")
      (description "单路、10MHz、CMOS、零温漂、零交叉、真 RRIO 精密运算放大器")
      (libsource (lib "custom") (part "TLV333IDBVR"))
    )
    (comp (ref "U7")
      (value "TPS7B6950QDBVRQ1")
      (footprint "SOT95P245X110-5N")
      (description "150mA 40V max input Ultra low Iq LDO,fixed   5V output AECQ100 Qualified")
      (libsource (lib "custom") (part "TPS7B6933DBVR"))
    )
    (comp (ref "U8")
      (value "CMS8S6990NA-QFN20")
      (footprint "QFN40P300X300X800_HS-21N")
      (description "增强型闪存1T 8051单片机，16KB Flash 256+1K XRAM")
      (libsource (lib "custom") (part "CM8S6990NA-QFN20"))
    )
    (comp (ref "U9")
      (value "OPA333AIDCKT")
      (footprint "SC70-5")
      (description "微功耗、1.8V、17uA 零漂移 CMOS 精密运算放大器")
      (libsource (lib "custom") (part "LMV321IDCKR"))
    )
    (comp (ref "U10")
      (value "CH412K")
      (footprint "SC70-6")
      (description "very low capacity quad IO ESD protection Array")
      (libsource (lib "custom") (part "CH412K"))
    )
    (comp (ref "U11")
      (value "LMV321IDCKR")
      (footprint "SC70-5")
      (description "CMOS超小型运算放大器，SC70-5")
      (libsource (lib "custom") (part "LMV321IDCKR"))
    )
    (comp (ref "U12")
      (value "LGS5148")
      (footprint "SOT95P245X110-6N")
      (description "48V输入，600mA同步降压转换器，SOT-23-6封装")
      (libsource (lib "custom") (part "LGS5148"))
    )
  )
  (nets
    (net (code "1") (name "/7892RUN") (class "Default")
      (node (ref "D8") (pin "1") (pinfunction "A_1") (pintype "passive"))
      (node (ref "R52") (pin "2") (pinfunction "2_2") (pintype "passive"))
      (node (ref "R53") (pin "2") (pinfunction "2_2") (pintype "passive"))
      (node (ref "U1") (pin "4") (pinfunction "RUN1_4") (pintype "input"))
      (node (ref "U1") (pin "5") (pinfunction "RUN2_5") (pintype "input"))
    )
    (net (code "2") (name "/ABst") (class "Default")
      (node (ref "C5") (pin "2") (pinfunction "2_2") (pintype "passive"))
      (node (ref "U2") (pin "1") (pinfunction "BST_1") (pintype "power_in"))
    )
    (net (code "3") (name "/ALx") (class "Default")
      (node (ref "C5") (pin "1") (pinfunction "1_1") (pintype "passive"))
      (node (ref "L3") (pin "2") (pinfunction "2_2") (pintype "passive"))
      (node (ref "U2") (pin "6") (pinfunction "SW_6") (pintype "power_in"))
    )
    (net (code "4") (name "/AUXFB") (class "Default")
      (node (ref "R4") (pin "2") (pinfunction "2_2") (pintype "passive"))
      (node (ref "R5") (pin "1") (pinfunction "1_1") (pintype "passive"))
      (node (ref "U2") (pin "3") (pinfunction "FB_3") (pintype "input"))
    )
    (net (code "5") (name "/BATFB") (class "Default")
      (node (ref "D3") (pin "2") (pinfunction "K_2") (pintype "passive"))
      (node (ref "R20") (pin "1") (pinfunction "1_1") (pintype "passive"))
      (node (ref "R22") (pin "2") (pinfunction "2_2") (pintype "passive"))
      (node (ref "U8") (pin "20") (pinfunction "P3.0/AN22/OP0_O/C0P4/C1P4_20") (pintype "bidirectional"))
    )
    (net (code "6") (name "/BG1") (class "Default")
      (node (ref "Q2") (pin "2") (pinfunction "G_2") (pintype "passive"))
      (node (ref "Q4") (pin "2") (pinfunction "G_2") (pintype "passive"))
      (node (ref "R6") (pin "2") (pinfunction "2_2") (pintype "passive"))
      (node (ref "R8") (pin "2") (pinfunction "2_2") (pintype "passive"))
    )
    (net (code "7") (name "/BG2") (class "Default")
      (node (ref "Q6") (pin "2") (pinfunction "G_2") (pintype "passive"))
      (node (ref "Q7") (pin "2") (pinfunction "G_2") (pintype "passive"))
      (node (ref "R44") (pin "2") (pinfunction "2_2") (pintype "passive"))
      (node (ref "R45") (pin "2") (pinfunction "2_2") (pintype "passive"))
    )
    (net (code "8") (name "/BGDN1") (class "Default")
      (node (ref "R8") (pin "1") (pinfunction "1_1") (pintype "passive"))
      (node (ref "U1") (pin "29") (pinfunction "BGDN1_29") (pintype "output"))
    )
    (net (code "9") (name "/BGDN2") (class "Default")
      (node (ref "R45") (pin "1") (pinfunction "1_1") (pintype "passive"))
      (node (ref "U1") (pin "22") (pinfunction "BGDN2_22") (pintype "output"))
    )
    (net (code "10") (name "/BGUP1") (class "Default")
      (node (ref "R6") (pin "1") (pinfunction "1_1") (pintype "passive"))
      (node (ref "U1") (pin "28") (pinfunction "BGUP1_28") (pintype "output"))
    )
    (net (code "11") (name "/BGUP2") (class "Default")
      (node (ref "R44") (pin "1") (pinfunction "1_1") (pintype "passive"))
      (node (ref "U1") (pin "23") (pinfunction "BGUP2_23") (pintype "output"))
    )
    (net (code "12") (name "/BST1") (class "Default")
      (node (ref "C10") (pin "1") (pinfunction "1_1") (pintype "passive"))
      (node (ref "D1") (pin "2") (pinfunction "K_2") (pintype "passive"))
      (node (ref "U1") (pin "30") (pinfunction "BST1_30") (pintype "power_in"))
    )
    (net (code "13") (name "/BST2") (class "Default")
      (node (ref "C62") (pin "1") (pinfunction "1_1") (pintype "passive"))
      (node (ref "D2") (pin "2") (pinfunction "K_2") (pintype "passive"))
      (node (ref "U1") (pin "21") (pinfunction "BST2_21") (pintype "power_in"))
    )
    (net (code "14") (name "/COMP") (class "Default")
      (node (ref "C17") (pin "2") (pinfunction "2_2") (pintype "passive"))
      (node (ref "R33") (pin "2") (pinfunction "2_2") (pintype "passive"))
      (node (ref "U1") (pin "37") (pinfunction "ITH1_37") (pintype "passive"))
    )
    (net (code "15") (name "/DCDCRUN") (class "Default")
      (node (ref "D8") (pin "2") (pinfunction "K_2") (pintype "passive"))
      (node (ref "R18") (pin "1") (pinfunction "1_1") (pintype "passive"))
      (node (ref "U12") (pin "4") (pinfunction "EN_4") (pintype "input"))
      (node (ref "U8") (pin "2") (pinfunction "P3.2/OP0_P/OSCOUT/AIN14_2") (pintype "bidirectional"))
    )
    (net (code "16") (name "/DCEN") (class "Default")
      (node (ref "R19") (pin "2") (pinfunction "2_2") (pintype "passive"))
      (node (ref "U2") (pin "4") (pinfunction "EN_4") (pintype "input"))
      (node (ref "U8") (pin "19") (pinfunction "P2.6/AN12/PGATO_19") (pintype "bidirectional"))
    )
    (net (code "17") (name "/DRVIN") (class "Default")
      (node (ref "C68") (pin "1") (pinfunction "1_1") (pintype "passive"))
      (node (ref "FB3") (pin "1") (pinfunction "1_1") (pintype "passive"))
      (node (ref "U12") (pin "5") (pinfunction "VIN_5") (pintype "power_in"))
    )
    (net (code "18") (name "/DSCK") (class "Default")
      (node (ref "U8") (pin "14") (pinfunction "DSCK/P2.1/AN21_14") (pintype "bidirectional"))
    )
    (net (code "19") (name "/DSDA") (class "Default")
      (node (ref "U8") (pin "4") (pinfunction "DSDA/P3.5/AN16_4") (pintype "bidirectional"))
    )
    (net (code "20") (name "/DTCA") (class "Default")
      (node (ref "R39") (pin "1") (pinfunction "1_1") (pintype "passive"))
      (node (ref "U1") (pin "9") (pinfunction "DTCA_9") (pintype "passive"))
    )
    (net (code "21") (name "/DTCB") (class "Default")
      (node (ref "R40") (pin "1") (pinfunction "1_1") (pintype "passive"))
      (node (ref "U1") (pin "10") (pinfunction "DTCB_10") (pintype "passive"))
    )
    (net (code "22") (name "/FSW") (class "Default")
      (node (ref "R35") (pin "1") (pinfunction "1_1") (pintype "passive"))
      (node (ref "U1") (pin "1") (pinfunction "FSW_1") (pintype "passive"))
    )
    (net (code "23") (name "/GH1") (class "Default")
      (node (ref "Q3") (pin "4") (pinfunction "G_4") (pintype "passive"))
      (node (ref "R10") (pin "2") (pinfunction "2_2") (pintype "passive"))
      (node (ref "R9") (pin "2") (pinfunction "2_2") (pintype "passive"))
    )
    (net (code "24") (name "/GH2") (class "Default")
      (node (ref "Q1") (pin "4") (pinfunction "G_4") (pintype "passive"))
      (node (ref "R46") (pin "2") (pinfunction "2_2") (pintype "passive"))
      (node (ref "R47") (pin "2") (pinfunction "2_2") (pintype "passive"))
    )
    (net (code "25") (name "/GLED") (class "Default")
      (node (ref "U10") (pin "1") (pinfunction "IO1_1") (pintype "passive"))
      (node (ref "U8") (pin "12") (pinfunction "AN6/C0P0/P1.3_12") (pintype "bidirectional"))
    )
    (net (code "26") (name "/HPath") (class "Default")
      (node (ref "Q5") (pin "1") (pinfunction "S_1") (pintype "passive"))
      (node (ref "Q5") (pin "2") (pinfunction "S_2") (pintype "passive"))
      (node (ref "Q5") (pin "3") (pinfunction "S_3") (pintype "passive"))
      (node (ref "R12") (pin "2") (pinfunction "2_2") (pintype "passive"))
      (node (ref "R13") (pin "1") (pinfunction "CIN_1") (pintype "passive"))
    )
    (net (code "27") (name "/ILED") (class "Default")
      (node (ref "U5") (pin "6") (pinfunction "VOUT_6") (pintype "output"))
      (node (ref "U6") (pin "3") (pinfunction "IN+_3") (pintype "input"))
    )
    (net (code "28") (name "/INJ") (class "Default")
      (node (ref "R14") (pin "1") (pinfunction "1_1") (pintype "passive"))
      (node (ref "U11") (pin "3") (pinfunction "IN-_3") (pintype "input"))
      (node (ref "U11") (pin "4") (pinfunction "OUT_4") (pintype "output"))
    )
    (net (code "29") (name "/IS1_N") (class "Default")
      (node (ref "R1") (pin "3") (pinfunction "CIN_3") (pintype "passive"))
      (node (ref "R7") (pin "2") (pinfunction "2_2") (pintype "passive"))
    )
    (net (code "30") (name "/IS1_P") (class "Default")
      (node (ref "C7") (pin "2") (pinfunction "2_2") (pintype "passive"))
      (node (ref "R1") (pin "2") (pinfunction "CIN_2") (pintype "passive"))
      (node (ref "U1") (pin "40") (pinfunction "SEN1_P_40") (pintype "input"))
    )
    (net (code "31") (name "/IS2_N") (class "Default")
      (node (ref "R2") (pin "2") (pinfunction "CIN_2") (pintype "passive"))
      (node (ref "R43") (pin "2") (pinfunction "2_2") (pintype "passive"))
    )
    (net (code "32") (name "/IS2_P") (class "Default")
      (node (ref "C48") (pin "2") (pinfunction "2_2") (pintype "passive"))
      (node (ref "R2") (pin "3") (pinfunction "CIN_3") (pintype "passive"))
      (node (ref "U1") (pin "11") (pinfunction "SEN2_P_11") (pintype "input"))
    )
    (net (code "33") (name "/KEY") (class "Default")
      (node (ref "R27") (pin "1") (pinfunction "1_1") (pintype "passive"))
      (node (ref "U10") (pin "6") (pinfunction "IO4_6") (pintype "passive"))
      (node (ref "U8") (pin "11") (pinfunction "C0P1/AN0/P0.0_11") (pintype "bidirectional"))
    )
    (net (code "34") (name "/LARGEIS_N") (class "Default")
      (node (ref "C70") (pin "2") (pinfunction "2_2") (pintype "passive"))
      (node (ref "R13") (pin "2") (pinfunction "CIN_2") (pintype "passive"))
      (node (ref "U5") (pin "5") (pinfunction "IN-_5") (pintype "input"))
    )
    (net (code "35") (name "/LARGEIS_P") (class "Default")
      (node (ref "C70") (pin "1") (pinfunction "1_1") (pintype "passive"))
      (node (ref "R13") (pin "3") (pinfunction "CIN_3") (pintype "passive"))
      (node (ref "U5") (pin "4") (pinfunction "IN+_4") (pintype "input"))
    )
    (net (code "36") (name "/LED-") (class "Default")
      (node (ref "Q5") (pin "5") (pinfunction "D_5") (pintype "passive"))
      (node (ref "Q5") (pin "6") (pinfunction "D_6") (pintype "passive"))
      (node (ref "Q5") (pin "7") (pinfunction "D_7") (pintype "passive"))
      (node (ref "Q5") (pin "8") (pinfunction "D_8") (pintype "passive"))
    )
    (net (code "37") (name "/LX1") (class "Default")
      (node (ref "C10") (pin "2") (pinfunction "2_2") (pintype "passive"))
      (node (ref "L1") (pin "2") (pinfunction "2_2") (pintype "passive"))
      (node (ref "Q2") (pin "3") (pinfunction "D_3") (pintype "passive"))
      (node (ref "Q3") (pin "1") (pinfunction "S_1") (pintype "passive"))
      (node (ref "Q3") (pin "2") (pinfunction "S_2") (pintype "passive"))
      (node (ref "Q3") (pin "3") (pinfunction "S_3") (pintype "passive"))
      (node (ref "Q4") (pin "3") (pinfunction "D_3") (pintype "passive"))
      (node (ref "R36") (pin "1") (pinfunction "1_1") (pintype "passive"))
      (node (ref "U1") (pin "31") (pinfunction "SW1_31") (pintype "power_in"))
    )
    (net (code "38") (name "/LX2") (class "Default")
      (node (ref "C62") (pin "2") (pinfunction "2_2") (pintype "passive"))
      (node (ref "L2") (pin "2") (pinfunction "2_2") (pintype "passive"))
      (node (ref "Q1") (pin "1") (pinfunction "S_1") (pintype "passive"))
      (node (ref "Q1") (pin "2") (pinfunction "S_2") (pintype "passive"))
      (node (ref "Q1") (pin "3") (pinfunction "S_3") (pintype "passive"))
      (node (ref "Q6") (pin "3") (pinfunction "D_3") (pintype "passive"))
      (node (ref "Q7") (pin "3") (pinfunction "D_3") (pintype "passive"))
      (node (ref "R37") (pin "1") (pinfunction "1_1") (pintype "passive"))
      (node (ref "U1") (pin "20") (pinfunction "SW2_20") (pintype "power_in"))
    )
    (net (code "39") (name "/LargeSEL") (class "Default")
      (node (ref "R54") (pin "2") (pinfunction "2_2") (pintype "passive"))
      (node (ref "R55") (pin "2") (pinfunction "2_2") (pintype "passive"))
      (node (ref "U3") (pin "1") (pinfunction "INP_1") (pintype "input"))
      (node (ref "U8") (pin "18") (pinfunction "P2.5/AN11_18") (pintype "bidirectional"))
    )
    (net (code "40") (name "/MODE") (class "Default")
      (node (ref "R38") (pin "1") (pinfunction "1_1") (pintype "passive"))
      (node (ref "U1") (pin "2") (pinfunction "MODE_2") (pintype "passive"))
    )
    (net (code "41") (name "/MOSG") (class "Default")
      (node (ref "Q5") (pin "4") (pinfunction "G_4") (pintype "passive"))
      (node (ref "R12") (pin "1") (pinfunction "1_1") (pintype "passive"))
      (node (ref "U3") (pin "4") (pinfunction "OUT_4") (pintype "power_in"))
      (node (ref "U3") (pin "5") (pinfunction "OUT_5") (pintype "power_in"))
    )
    (net (code "42") (name "/OPOUT") (class "Default")
      (node (ref "C37") (pin "2") (pinfunction "2_2") (pintype "passive"))
      (node (ref "R16") (pin "2") (pinfunction "2_2") (pintype "passive"))
      (node (ref "R17") (pin "1") (pinfunction "1_1") (pintype "passive"))
      (node (ref "R28") (pin "1") (pinfunction "1_1") (pintype "passive"))
      (node (ref "U6") (pin "1") (pinfunction "OUT_1") (pintype "output"))
    )
    (net (code "43") (name "/OPVCC") (class "Default")
      (node (ref "C43") (pin "2") (pinfunction "2_2") (pintype "passive"))
      (node (ref "D4") (pin "3") (pinfunction "K_3") (pintype "passive"))
      (node (ref "R26") (pin "2") (pinfunction "2_2") (pintype "passive"))
      (node (ref "U8") (pin "16") (pinfunction "P2.3/AN9/OP1N_16") (pintype "bidirectional"))
      (node (ref "U9") (pin "5") (pinfunction "VCC_5") (pintype "power_in"))
    )
    (net (code "44") (name "/OUTFB") (class "Default")
      (node (ref "R21") (pin "1") (pinfunction "1_1") (pintype "passive"))
      (node (ref "R23") (pin "2") (pinfunction "2_2") (pintype "passive"))
      (node (ref "U8") (pin "1") (pinfunction "P3.1/OP0_N/OSCIN/AIN13_1") (pintype "bidirectional"))
    )
    (net (code "45") (name "/PWM") (class "Default")
      (node (ref "R24") (pin "1") (pinfunction "1_1") (pintype "passive"))
      (node (ref "U8") (pin "15") (pinfunction "P2.2/AN8/OP1P_15") (pintype "bidirectional"))
    )
    (net (code "46") (name "/PrechargeEN") (class "Default")
      (node (ref "R32") (pin "2") (pinfunction "2_2") (pintype "passive"))
      (node (ref "U8") (pin "9") (pinfunction "C1P2/AN2/P0.2_9") (pintype "bidirectional"))
    )
    (net (code "47") (name "/RLED") (class "Default")
      (node (ref "U10") (pin "3") (pinfunction "IO2_3") (pintype "passive"))
      (node (ref "U8") (pin "13") (pinfunction "AN7/C0N/P1.4_13") (pintype "bidirectional"))
    )
    (net (code "48") (name "/SENAN") (class "Default")
      (node (ref "C7") (pin "1") (pinfunction "1_1") (pintype "passive"))
      (node (ref "R7") (pin "1") (pinfunction "1_1") (pintype "passive"))
      (node (ref "U1") (pin "39") (pinfunction "SEN1_N_39") (pintype "input"))
    )
    (net (code "49") (name "/SENBN") (class "Default")
      (node (ref "C48") (pin "1") (pinfunction "1_1") (pintype "passive"))
      (node (ref "R43") (pin "1") (pinfunction "1_1") (pintype "passive"))
      (node (ref "U1") (pin "12") (pinfunction "SEN2_N_12") (pintype "input"))
    )
    (net (code "50") (name "/SS1") (class "Default")
      (node (ref "C18") (pin "2") (pinfunction "2_2") (pintype "passive"))
      (node (ref "U1") (pin "36") (pinfunction "SS1_36") (pintype "passive"))
    )
    (net (code "51") (name "/SYSHB") (class "Default")
      (node (ref "R31") (pin "2") (pinfunction "2_2") (pintype "passive"))
      (node (ref "U8") (pin "7") (pinfunction "C1P0/AN4/P0.4_7") (pintype "bidirectional"))
    )
    (net (code "52") (name "/TBST") (class "Default")
      (node (ref "C69") (pin "2") (pinfunction "2_2") (pintype "passive"))
      (node (ref "U12") (pin "1") (pinfunction "BST_1") (pintype "power_in"))
    )
    (net (code "53") (name "/TFB") (class "Default")
      (node (ref "R50") (pin "1") (pinfunction "1_1") (pintype "passive"))
      (node (ref "R51") (pin "2") (pinfunction "2_2") (pintype "passive"))
      (node (ref "U12") (pin "3") (pinfunction "FB_3") (pintype "input"))
    )
    (net (code "54") (name "/TGDN1") (class "Default")
      (node (ref "R10") (pin "1") (pinfunction "1_1") (pintype "passive"))
      (node (ref "U1") (pin "32") (pinfunction "TGDN1_32") (pintype "output"))
    )
    (net (code "55") (name "/TGDN2") (class "Default")
      (node (ref "R47") (pin "1") (pinfunction "1_1") (pintype "passive"))
      (node (ref "U1") (pin "19") (pinfunction "TGDN2_19") (pintype "output"))
    )
    (net (code "56") (name "/TGUP1") (class "Default")
      (node (ref "R9") (pin "1") (pinfunction "1_1") (pintype "passive"))
      (node (ref "U1") (pin "33") (pinfunction "TGUP1_33") (pintype "output"))
    )
    (net (code "57") (name "/TGUP2") (class "Default")
      (node (ref "R46") (pin "1") (pinfunction "1_1") (pintype "passive"))
      (node (ref "U1") (pin "18") (pinfunction "TGUP2_18") (pintype "output"))
    )
    (net (code "58") (name "/TLX") (class "Default")
      (node (ref "C69") (pin "1") (pinfunction "1_1") (pintype "passive"))
      (node (ref "L4") (pin "2") (pinfunction "2_2") (pintype "passive"))
      (node (ref "U12") (pin "6") (pinfunction "SW_6") (pintype "power_in"))
    )
    (net (code "59") (name "/TSEN") (class "Default")
      (node (ref "R29") (pin "2") (pinfunction "2_2") (pintype "passive"))
      (node (ref "U8") (pin "8") (pinfunction "C1P1/AN3/P0.3_8") (pintype "bidirectional"))
    )
    (net (code "60") (name "/TempSen") (class "Default")
      (node (ref "C47") (pin "2") (pinfunction "2_2") (pintype "passive"))
      (node (ref "R29") (pin "1") (pinfunction "1_1") (pintype "passive"))
      (node (ref "R30") (pin "2") (pinfunction "2_2") (pintype "passive"))
      (node (ref "U8") (pin "6") (pinfunction "C1N/AN5/P0.5_6") (pintype "bidirectional"))
    )
    (net (code "61") (name "/VFB") (class "Default")
      (node (ref "R11") (pin "2") (pinfunction "2_2") (pintype "passive"))
      (node (ref "R14") (pin "2") (pinfunction "2_2") (pintype "passive"))
      (node (ref "R17") (pin "2") (pinfunction "2_2") (pintype "passive"))
      (node (ref "R41") (pin "2") (pinfunction "2_2") (pintype "passive"))
      (node (ref "U1") (pin "38") (pinfunction "VFB1_38") (pintype "input"))
    )
    (net (code "62") (name "/VOP") (class "Default")
      (node (ref "C46") (pin "2") (pinfunction "2_2") (pintype "passive"))
      (node (ref "R28") (pin "2") (pinfunction "2_2") (pintype "passive"))
      (node (ref "U8") (pin "10") (pinfunction "C0P2/AN1/P0.1_10") (pintype "bidirectional"))
    )
    (net (code "63") (name "/VREF") (class "Default")
      (node (ref "R15") (pin "1") (pinfunction "1_1") (pintype "passive"))
      (node (ref "U9") (pin "3") (pinfunction "IN-_3") (pintype "input"))
      (node (ref "U9") (pin "4") (pinfunction "OUT_4") (pintype "output"))
    )
    (net (code "64") (name "5VFB") (class "Default")
      (node (ref "C34") (pin "2") (pinfunction "2_2") (pintype "passive"))
      (node (ref "C36") (pin "2") (pinfunction "2_2") (pintype "passive"))
      (node (ref "C38") (pin "1") (pinfunction "1_1") (pintype "passive"))
      (node (ref "C49") (pin "2") (pinfunction "2_2") (pintype "passive"))
      (node (ref "U1") (pin "13") (pinfunction "VFB2_13") (pintype "input"))
      (node (ref "U11") (pin "5") (pinfunction "VCC_5") (pintype "power_in"))
      (node (ref "U4") (pin "5") (pinfunction "VOUT_5") (pintype "power_in"))
      (node (ref "U5") (pin "3") (pinfunction "VS_3") (pintype "passive"))
      (node (ref "U6") (pin "5") (pinfunction "VDD_5") (pintype "power_in"))
    )
    (net (code "65") (name "6V0") (class "Default")
      (node (ref "C12") (pin "1") (pinfunction "1_1") (pintype "passive"))
      (node (ref "C42") (pin "2") (pinfunction "2_2") (pintype "passive"))
      (node (ref "C55") (pin "1") (pinfunction "1_1") (pintype "passive"))
      (node (ref "C72") (pin "2") (pinfunction "2_2") (pintype "passive"))
      (node (ref "C74") (pin "1") (pinfunction "1_1") (pintype "passive"))
      (node (ref "C8") (pin "2") (pinfunction "2_2") (pintype "passive"))
      (node (ref "FB1") (pin "1") (pinfunction "1_1") (pintype "passive"))
      (node (ref "L3") (pin "1") (pinfunction "1_1") (pintype "passive"))
      (node (ref "R4") (pin "1") (pinfunction "1_1") (pintype "passive"))
      (node (ref "U1") (pin "26") (pinfunction "EXTVCC_26") (pintype "power_in"))
      (node (ref "U1") (pin "27") (pinfunction "VBIAS_27") (pintype "power_in"))
      (node (ref "U3") (pin "6") (pinfunction "VDD_6") (pintype "power_in"))
      (node (ref "U3") (pin "7") (pinfunction "VDD_7") (pintype "power_in"))
    )
    (net (code "66") (name "12V") (class "Default")
      (node (ref "C1") (pin "1") (pinfunction "1_1") (pintype "passive"))
      (node (ref "C11") (pin "2") (pinfunction "2_2") (pintype "passive"))
      (node (ref "C13") (pin "2") (pinfunction "2_2") (pintype "passive"))
      (node (ref "C14") (pin "2") (pinfunction "2_2") (pintype "passive"))
      (node (ref "C2") (pin "1") (pinfunction "1_1") (pintype "passive"))
      (node (ref "C25") (pin "2") (pinfunction "2_2") (pintype "passive"))
      (node (ref "C26") (pin "2") (pinfunction "2_2") (pintype "passive"))
      (node (ref "C27") (pin "2") (pinfunction "2_2") (pintype "passive"))
      (node (ref "C28") (pin "2") (pinfunction "2_2") (pintype "passive"))
      (node (ref "C29") (pin "2") (pinfunction "2_2") (pintype "passive"))
      (node (ref "C30") (pin "2") (pinfunction "2_2") (pintype "passive"))
      (node (ref "C57") (pin "2") (pinfunction "2_2") (pintype "passive"))
      (node (ref "C65") (pin "2") (pinfunction "2_2") (pintype "passive"))
      (node (ref "C73") (pin "2") (pinfunction "2_2") (pintype "passive"))
      (node (ref "D6") (pin "2") (pinfunction "A1_2") (pintype "passive"))
      (node (ref "D6") (pin "3") (pinfunction "A2_3") (pintype "passive"))
      (node (ref "D7") (pin "1") (pinfunction "A_1") (pintype "passive"))
      (node (ref "FB3") (pin "2") (pinfunction "2_2") (pintype "passive"))
      (node (ref "R1") (pin "0") (pinfunction "CIN_0") (pintype "passive"))
      (node (ref "R2") (pin "1") (pinfunction "CIN_1") (pintype "passive"))
      (node (ref "R20") (pin "2") (pinfunction "2_2") (pintype "passive"))
      (node (ref "R3") (pin "2") (pinfunction "2_2") (pintype "passive"))
    )
    (net (code "67") (name "DRVCC") (class "Default")
      (node (ref "C15") (pin "2") (pinfunction "2_2") (pintype "passive"))
      (node (ref "C61") (pin "2") (pinfunction "2_2") (pintype "passive"))
      (node (ref "C63") (pin "2") (pinfunction "2_2") (pintype "passive"))
      (node (ref "C64") (pin "2") (pinfunction "2_2") (pintype "passive"))
      (node (ref "C71") (pin "2") (pinfunction "2_2") (pintype "passive"))
      (node (ref "C75") (pin "2") (pinfunction "2_2") (pintype "passive"))
      (node (ref "D10") (pin "2") (pinfunction "K_2") (pintype "passive"))
      (node (ref "L4") (pin "1") (pinfunction "1_1") (pintype "passive"))
      (node (ref "R48") (pin "2") (pinfunction "2_2") (pintype "passive"))
      (node (ref "R49") (pin "1") (pinfunction "1_1") (pintype "passive"))
      (node (ref "R50") (pin "2") (pinfunction "2_2") (pintype "passive"))
      (node (ref "R53") (pin "1") (pinfunction "1_1") (pintype "passive"))
      (node (ref "U1") (pin "24") (pinfunction "DRVCC_24") (pintype "power_in"))
    )
    (net (code "68") (name "GND") (class "Default")
      (node (ref "C1") (pin "2") (pinfunction "2_2") (pintype "passive"))
      (node (ref "C11") (pin "1") (pinfunction "1_1") (pintype "passive"))
      (node (ref "C12") (pin "2") (pinfunction "2_2") (pintype "passive"))
      (node (ref "C13") (pin "1") (pinfunction "1_1") (pintype "passive"))
      (node (ref "C14") (pin "1") (pinfunction "1_1") (pintype "passive"))
      (node (ref "C15") (pin "1") (pinfunction "1_1") (pintype "passive"))
      (node (ref "C16") (pin "2") (pinfunction "2_2") (pintype "passive"))
      (node (ref "C17") (pin "1") (pinfunction "1_1") (pintype "passive"))
      (node (ref "C18") (pin "1") (pinfunction "1_1") (pintype "passive"))
      (node (ref "C19") (pin "1") (pinfunction "1_1") (pintype "passive"))
      (node (ref "C2") (pin "2") (pinfunction "2_2") (pintype "passive"))
      (node (ref "C20") (pin "1") (pinfunction "1_1") (pintype "passive"))
      (node (ref "C21") (pin "1") (pinfunction "1_1") (pintype "passive"))
      (node (ref "C22") (pin "1") (pinfunction "1_1") (pintype "passive"))
      (node (ref "C23") (pin "1") (pinfunction "1_1") (pintype "passive"))
      (node (ref "C24") (pin "1") (pinfunction "1_1") (pintype "passive"))
      (node (ref "C25") (pin "1") (pinfunction "1_1") (pintype "passive"))
      (node (ref "C26") (pin "1") (pinfunction "1_1") (pintype "passive"))
      (node (ref "C27") (pin "1") (pinfunction "1_1") (pintype "passive"))
      (node (ref "C28") (pin "1") (pinfunction "1_1") (pintype "passive"))
      (node (ref "C29") (pin "1") (pinfunction "1_1") (pintype "passive"))
      (node (ref "C3") (pin "2") (pinfunction "2_2") (pintype "passive"))
      (node (ref "C30") (pin "1") (pinfunction "1_1") (pintype "passive"))
      (node (ref "C31") (pin "1") (pinfunction "1_1") (pintype "passive"))
      (node (ref "C32") (pin "1") (pinfunction "1_1") (pintype "passive"))
      (node (ref "C34") (pin "1") (pinfunction "1_1") (pintype "passive"))
      (node (ref "C35") (pin "1") (pinfunction "1_1") (pintype "passive"))
      (node (ref "C36") (pin "1") (pinfunction "1_1") (pintype "passive"))
      (node (ref "C38") (pin "2") (pinfunction "2_2") (pintype "passive"))
      (node (ref "C39") (pin "1") (pinfunction "1_1") (pintype "passive"))
      (node (ref "C4") (pin "2") (pinfunction "2_2") (pintype "passive"))
      (node (ref "C40") (pin "1") (pinfunction "1_1") (pintype "passive"))
      (node (ref "C41") (pin "1") (pinfunction "1_1") (pintype "passive"))
      (node (ref "C42") (pin "1") (pinfunction "1_1") (pintype "passive"))
      (node (ref "C43") (pin "1") (pinfunction "1_1") (pintype "passive"))
      (node (ref "C44") (pin "1") (pinfunction "1_1") (pintype "passive"))
      (node (ref "C45") (pin "1") (pinfunction "1_1") (pintype "passive"))
      (node (ref "C46") (pin "1") (pinfunction "1_1") (pintype "passive"))
      (node (ref "C47") (pin "1") (pinfunction "1_1") (pintype "passive"))
      (node (ref "C49") (pin "1") (pinfunction "1_1") (pintype "passive"))
      (node (ref "C51") (pin "1") (pinfunction "1_1") (pintype "passive"))
      (node (ref "C52") (pin "1") (pinfunction "1_1") (pintype "passive"))
      (node (ref "C53") (pin "1") (pinfunction "1_1") (pintype "passive"))
      (node (ref "C54") (pin "1") (pinfunction "1_1") (pintype "passive"))
      (node (ref "C55") (pin "2") (pinfunction "2_2") (pintype "passive"))
      (node (ref "C56") (pin "1") (pinfunction "1_1") (pintype "passive"))
      (node (ref "C57") (pin "1") (pinfunction "1_1") (pintype "passive"))
      (node (ref "C58") (pin "1") (pinfunction "1_1") (pintype "passive"))
      (node (ref "C59") (pin "2") (pinfunction "2_2") (pintype "passive"))
      (node (ref "C6") (pin "1") (pinfunction "1_1") (pintype "passive"))
      (node (ref "C60") (pin "2") (pinfunction "2_2") (pintype "passive"))
      (node (ref "C61") (pin "1") (pinfunction "1_1") (pintype "passive"))
      (node (ref "C63") (pin "1") (pinfunction "1_1") (pintype "passive"))
      (node (ref "C64") (pin "1") (pinfunction "1_1") (pintype "passive"))
      (node (ref "C65") (pin "1") (pinfunction "1_1") (pintype "passive"))
      (node (ref "C66") (pin "1") (pinfunction "1_1") (pintype "passive"))
      (node (ref "C67") (pin "1") (pinfunction "1_1") (pintype "passive"))
      (node (ref "C68") (pin "2") (pinfunction "2_2") (pintype "passive"))
      (node (ref "C71") (pin "1") (pinfunction "1_1") (pintype "passive"))
      (node (ref "C72") (pin "1") (pinfunction "1_1") (pintype "passive"))
      (node (ref "C73") (pin "1") (pinfunction "1_1") (pintype "passive"))
      (node (ref "C74") (pin "2") (pinfunction "2_2") (pintype "passive"))
      (node (ref "C75") (pin "1") (pinfunction "1_1") (pintype "passive"))
      (node (ref "C8") (pin "1") (pinfunction "1_1") (pintype "passive"))
      (node (ref "C9") (pin "1") (pinfunction "1_1") (pintype "passive"))
      (node (ref "D10") (pin "1") (pinfunction "A_1") (pintype "passive"))
      (node (ref "D3") (pin "1") (pinfunction "A_1") (pintype "passive"))
      (node (ref "D5") (pin "K") (pinfunction "K_K") (pintype "passive"))
      (node (ref "D9") (pin "K") (pinfunction "K_K") (pintype "passive"))
      (node (ref "Q2") (pin "1") (pinfunction "S_1") (pintype "passive"))
      (node (ref "Q4") (pin "1") (pinfunction "S_1") (pintype "passive"))
      (node (ref "Q6") (pin "1") (pinfunction "S_1") (pintype "passive"))
      (node (ref "Q7") (pin "1") (pinfunction "S_1") (pintype "passive"))
      (node (ref "R11") (pin "1") (pinfunction "1_1") (pintype "passive"))
      (node (ref "R13") (pin "0") (pinfunction "CIN_0") (pintype "passive"))
      (node (ref "R18") (pin "2") (pinfunction "2_2") (pintype "passive"))
      (node (ref "R19") (pin "1") (pinfunction "1_1") (pintype "passive"))
      (node (ref "R22") (pin "1") (pinfunction "1_1") (pintype "passive"))
      (node (ref "R23") (pin "1") (pinfunction "1_1") (pintype "passive"))
      (node (ref "R26") (pin "1") (pinfunction "1_1") (pintype "passive"))
      (node (ref "R30") (pin "1") (pinfunction "1_1") (pintype "passive"))
      (node (ref "R35") (pin "2") (pinfunction "2_2") (pintype "passive"))
      (node (ref "R39") (pin "2") (pinfunction "2_2") (pintype "passive"))
      (node (ref "R40") (pin "2") (pinfunction "2_2") (pintype "passive"))
      (node (ref "R5") (pin "2") (pinfunction "2_2") (pintype "passive"))
      (node (ref "R51") (pin "1") (pinfunction "1_1") (pintype "passive"))
      (node (ref "R52") (pin "1") (pinfunction "1_1") (pintype "passive"))
      (node (ref "R55") (pin "1") (pinfunction "1_1") (pintype "passive"))
      (node (ref "U1") (pin "14") (pinfunction "ITH2_14") (pintype "passive"))
      (node (ref "U1") (pin "15") (pinfunction "SS2_15") (pintype "passive"))
      (node (ref "U1") (pin "17") (pinfunction "PGOOD2_17") (pintype "passive"))
      (node (ref "U1") (pin "3") (pinfunction "PLLIN/SPR_3") (pintype "input"))
      (node (ref "U1") (pin "34") (pinfunction "PGOOD1_34") (pintype "passive"))
      (node (ref "U1") (pin "41") (pinfunction "EP/GND_41") (pintype "passive"))
      (node (ref "U1") (pin "6") (pinfunction "GND_6") (pintype "passive"))
      (node (ref "U1") (pin "7") (pinfunction "UVLO_7") (pintype "input"))
      (node (ref "U1") (pin "8") (pinfunction "DRVSET_8") (pintype "input"))
      (node (ref "U10") (pin "2") (pinfunction "GND_2") (pintype "passive"))
      (node (ref "U11") (pin "2") (pinfunction "GND_2") (pintype "power_in"))
      (node (ref "U12") (pin "2") (pinfunction "GND_2") (pintype "power_in"))
      (node (ref "U2") (pin "2") (pinfunction "GND_2") (pintype "power_in"))
      (node (ref "U3") (pin "2") (pinfunction "GND_2") (pintype "power_in"))
      (node (ref "U3") (pin "3") (pinfunction "GND_3") (pintype "power_in"))
      (node (ref "U3") (pin "8") (pinfunction "INN_8") (pintype "input"))
      (node (ref "U3") (pin "9") (pinfunction "EP/GND_9") (pintype "power_in"))
      (node (ref "U4") (pin "3") (pinfunction "GND_3") (pintype "power_in"))
      (node (ref "U4") (pin "4") (pinfunction "GND_4") (pintype "power_in"))
      (node (ref "U5") (pin "1") (pinfunction "REF_1") (pintype "passive"))
      (node (ref "U5") (pin "2") (pinfunction "GND_2") (pintype "passive"))
      (node (ref "U6") (pin "2") (pinfunction "VSS_2") (pintype "power_in"))
      (node (ref "U7") (pin "3") (pinfunction "GND_3") (pintype "power_in"))
      (node (ref "U7") (pin "4") (pinfunction "GND_4") (pintype "power_in"))
      (node (ref "U8") (pin "21") (pinfunction "GND/EPAD_21") (pintype "power_in"))
      (node (ref "U8") (pin "3") (pinfunction "VSS_3") (pintype "power_in"))
      (node (ref "U9") (pin "2") (pinfunction "GND_2") (pintype "power_in"))
    )
    (net (code "69") (name "INTVCC") (class "Default")
      (node (ref "C9") (pin "2") (pinfunction "2_2") (pintype "passive"))
      (node (ref "R38") (pin "2") (pinfunction "2_2") (pintype "passive"))
      (node (ref "U1") (pin "25") (pinfunction "INTVCCO_25") (pintype "power_in"))
    )
    (net (code "70") (name "MCU5V") (class "Default")
      (node (ref "C39") (pin "2") (pinfunction "2_2") (pintype "passive"))
      (node (ref "C41") (pin "2") (pinfunction "2_2") (pintype "passive"))
      (node (ref "R27") (pin "2") (pinfunction "2_2") (pintype "passive"))
      (node (ref "U10") (pin "5") (pinfunction "VCC_5") (pintype "passive"))
      (node (ref "U7") (pin "5") (pinfunction "VOUT_5") (pintype "power_in"))
      (node (ref "U8") (pin "5") (pinfunction "VDD_5") (pintype "power_in"))
    )
    (net (code "71") (name "Net-(C31-Pad2)") (class "Default")
      (node (ref "C31") (pin "2") (pinfunction "2_2") (pintype "passive"))
      (node (ref "R33") (pin "1") (pinfunction "1_1") (pintype "passive"))
    )
    (net (code "72") (name "Net-(C33-Pad2)") (class "Default")
      (node (ref "C33") (pin "2") (pinfunction "2_2") (pintype "passive"))
      (node (ref "R41") (pin "1") (pinfunction "1_1") (pintype "passive"))
      (node (ref "R42") (pin "2") (pinfunction "2_2") (pintype "passive"))
    )
    (net (code "73") (name "Net-(C44-Pad2)") (class "Default")
      (node (ref "C44") (pin "2") (pinfunction "2_2") (pintype "passive"))
      (node (ref "D4") (pin "1") (pinfunction "A_1") (pintype "passive"))
      (node (ref "R24") (pin "2") (pinfunction "2_2") (pintype "passive"))
      (node (ref "R25") (pin "1") (pinfunction "1_1") (pintype "passive"))
    )
    (net (code "74") (name "Net-(C59-Pad1)") (class "Default")
      (node (ref "C59") (pin "1") (pinfunction "1_1") (pintype "passive"))
      (node (ref "R36") (pin "2") (pinfunction "2_2") (pintype "passive"))
    )
    (net (code "75") (name "Net-(C60-Pad1)") (class "Default")
      (node (ref "C60") (pin "1") (pinfunction "1_1") (pintype "passive"))
      (node (ref "R37") (pin "2") (pinfunction "2_2") (pintype "passive"))
    )
    (net (code "76") (name "Net-(D1-A)") (class "Default")
      (node (ref "D1") (pin "1") (pinfunction "A_1") (pintype "passive"))
      (node (ref "R49") (pin "2") (pinfunction "2_2") (pintype "passive"))
    )
    (net (code "77") (name "Net-(D2-A)") (class "Default")
      (node (ref "D2") (pin "1") (pinfunction "A_1") (pintype "passive"))
      (node (ref "R48") (pin "1") (pinfunction "1_1") (pintype "passive"))
    )
    (net (code "78") (name "Net-(D5-PadA)") (class "Default")
      (node (ref "D5") (pin "A") (pinfunction "A_A") (pintype "passive"))
      (node (ref "R31") (pin "1") (pinfunction "1_1") (pintype "passive"))
    )
    (net (code "79") (name "Net-(D7-K)") (class "Default")
      (node (ref "D7") (pin "2") (pinfunction "K_2") (pintype "passive"))
      (node (ref "FB2") (pin "1") (pinfunction "1_1") (pintype "passive"))
    )
    (net (code "80") (name "Net-(D9-PadA)") (class "Default")
      (node (ref "D9") (pin "A") (pinfunction "A_A") (pintype "passive"))
      (node (ref "R54") (pin "1") (pinfunction "1_1") (pintype "passive"))
    )
    (net (code "81") (name "Net-(L1-Pad1)") (class "Default")
      (node (ref "L1") (pin "1") (pinfunction "1_1") (pintype "passive"))
      (node (ref "R1") (pin "1") (pinfunction "CIN_1") (pintype "passive"))
    )
    (net (code "82") (name "Net-(L2-Pad1)") (class "Default")
      (node (ref "L2") (pin "1") (pinfunction "1_1") (pintype "passive"))
      (node (ref "R2") (pin "0") (pinfunction "CIN_0") (pintype "passive"))
    )
    (net (code "83") (name "Net-(R21-Pad2)") (class "Default")
      (node (ref "R21") (pin "2") (pinfunction "2_2") (pintype "passive"))
      (node (ref "R34") (pin "1") (pinfunction "1_1") (pintype "passive"))
    )
    (net (code "84") (name "Net-(U2-VIN)") (class "Default")
      (node (ref "C6") (pin "2") (pinfunction "2_2") (pintype "passive"))
      (node (ref "R3") (pin "1") (pinfunction "1_1") (pintype "passive"))
      (node (ref "U2") (pin "5") (pinfunction "VIN_5") (pintype "power_in"))
    )
    (net (code "85") (name "Net-(U4-VIN)") (class "Default")
      (node (ref "C35") (pin "2") (pinfunction "2_2") (pintype "passive"))
      (node (ref "FB1") (pin "2") (pinfunction "2_2") (pintype "passive"))
      (node (ref "U4") (pin "1") (pinfunction "VIN_1") (pintype "power_in"))
    )
    (net (code "86") (name "Net-(U6-IN-)") (class "Default")
      (node (ref "C37") (pin "1") (pinfunction "1_1") (pintype "passive"))
      (node (ref "R15") (pin "2") (pinfunction "2_2") (pintype "passive"))
      (node (ref "R16") (pin "1") (pinfunction "1_1") (pintype "passive"))
      (node (ref "U6") (pin "4") (pinfunction "IN-_4") (pintype "input"))
    )
    (net (code "87") (name "Net-(U7-VIN)") (class "Default")
      (node (ref "C40") (pin "2") (pinfunction "2_2") (pintype "passive"))
      (node (ref "FB2") (pin "2") (pinfunction "2_2") (pintype "passive"))
      (node (ref "U7") (pin "1") (pinfunction "VIN_1") (pintype "power_in"))
    )
    (net (code "88") (name "Net-(U9-IN+)") (class "Default")
      (node (ref "C45") (pin "2") (pinfunction "2_2") (pintype "passive"))
      (node (ref "D4") (pin "2") (pinfunction "A_2") (pintype "passive"))
      (node (ref "R25") (pin "2") (pinfunction "2_2") (pintype "passive"))
      (node (ref "U9") (pin "1") (pinfunction "IN+_1") (pintype "input"))
    )
    (net (code "89") (name "Net-(U11-IN+)") (class "Default")
      (node (ref "C56") (pin "2") (pinfunction "2_2") (pintype "passive"))
      (node (ref "R32") (pin "1") (pinfunction "1_1") (pintype "passive"))
      (node (ref "U11") (pin "1") (pinfunction "IN+_1") (pintype "input"))
    )
    (net (code "90") (name "VOUT") (class "Default")
      (node (ref "C16") (pin "1") (pinfunction "1_1") (pintype "passive"))
      (node (ref "C19") (pin "2") (pinfunction "2_2") (pintype "passive"))
      (node (ref "C20") (pin "2") (pinfunction "2_2") (pintype "passive"))
      (node (ref "C21") (pin "2") (pinfunction "2_2") (pintype "passive"))
      (node (ref "C22") (pin "2") (pinfunction "2_2") (pintype "passive"))
      (node (ref "C23") (pin "2") (pinfunction "2_2") (pintype "passive"))
      (node (ref "C24") (pin "2") (pinfunction "2_2") (pintype "passive"))
      (node (ref "C3") (pin "1") (pinfunction "1_1") (pintype "passive"))
      (node (ref "C32") (pin "2") (pinfunction "2_2") (pintype "passive"))
      (node (ref "C33") (pin "1") (pinfunction "1_1") (pintype "passive"))
      (node (ref "C4") (pin "1") (pinfunction "1_1") (pintype "passive"))
      (node (ref "C51") (pin "2") (pinfunction "2_2") (pintype "passive"))
      (node (ref "C52") (pin "2") (pinfunction "2_2") (pintype "passive"))
      (node (ref "C53") (pin "2") (pinfunction "2_2") (pintype "passive"))
      (node (ref "C54") (pin "2") (pinfunction "2_2") (pintype "passive"))
      (node (ref "C58") (pin "2") (pinfunction "2_2") (pintype "passive"))
      (node (ref "C66") (pin "2") (pinfunction "2_2") (pintype "passive"))
      (node (ref "C67") (pin "2") (pinfunction "2_2") (pintype "passive"))
      (node (ref "D6") (pin "1") (pinfunction "K_1") (pintype "passive"))
      (node (ref "Q1") (pin "5") (pinfunction "D_5") (pintype "passive"))
      (node (ref "Q1") (pin "6") (pinfunction "D_6") (pintype "passive"))
      (node (ref "Q1") (pin "7") (pinfunction "D_7") (pintype "passive"))
      (node (ref "Q1") (pin "8") (pinfunction "D_8") (pintype "passive"))
      (node (ref "Q3") (pin "5") (pinfunction "D_5") (pintype "passive"))
      (node (ref "Q3") (pin "6") (pinfunction "D_6") (pintype "passive"))
      (node (ref "Q3") (pin "7") (pinfunction "D_7") (pintype "passive"))
      (node (ref "Q3") (pin "8") (pinfunction "D_8") (pintype "passive"))
      (node (ref "R34") (pin "2") (pinfunction "2_2") (pintype "passive"))
      (node (ref "R42") (pin "1") (pinfunction "1_1") (pintype "passive"))
    )
    (net (code "91") (name "unconnected-(U1C-ILIM-Pad16)") (class "Default")
      (node (ref "U1") (pin "16") (pinfunction "ILIM_16") (pintype "passive+no_connect"))
    )
    (net (code "92") (name "unconnected-(U1D-VPRG1-Pad35)") (class "Default")
      (node (ref "U1") (pin "35") (pinfunction "VPRG1_35") (pintype "passive+no_connect"))
    )
    (net (code "93") (name "unconnected-(U4-NC-Pad2)") (class "Default")
      (node (ref "U4") (pin "2") (pinfunction "NC_2") (pintype "passive+no_connect"))
    )
    (net (code "94") (name "unconnected-(U7-NC-Pad2)") (class "Default")
      (node (ref "U7") (pin "2") (pinfunction "NC_2") (pintype "passive+no_connect"))
    )
    (net (code "95") (name "unconnected-(U8D-P2.4{slash}AN10{slash}OP1O{slash}C0P5{slash}C1P5-Pad17)") (class "Default")
      (node (ref "U8") (pin "17") (pinfunction "P2.4/AN10/OP1O/C0P5/C1P5_17") (pintype "bidirectional+no_connect"))
    )
    (net (code "96") (name "unconnected-(U10-IO3-Pad4)") (class "Default")
      (node (ref "U10") (pin "4") (pinfunction "IO3_4") (pintype "passive+no_connect"))
    )
  )
)
